# SCH_LED-bargraph-1_7_2024-11-25.net
KiCad netlist of a schematic drawn in EasyEDA
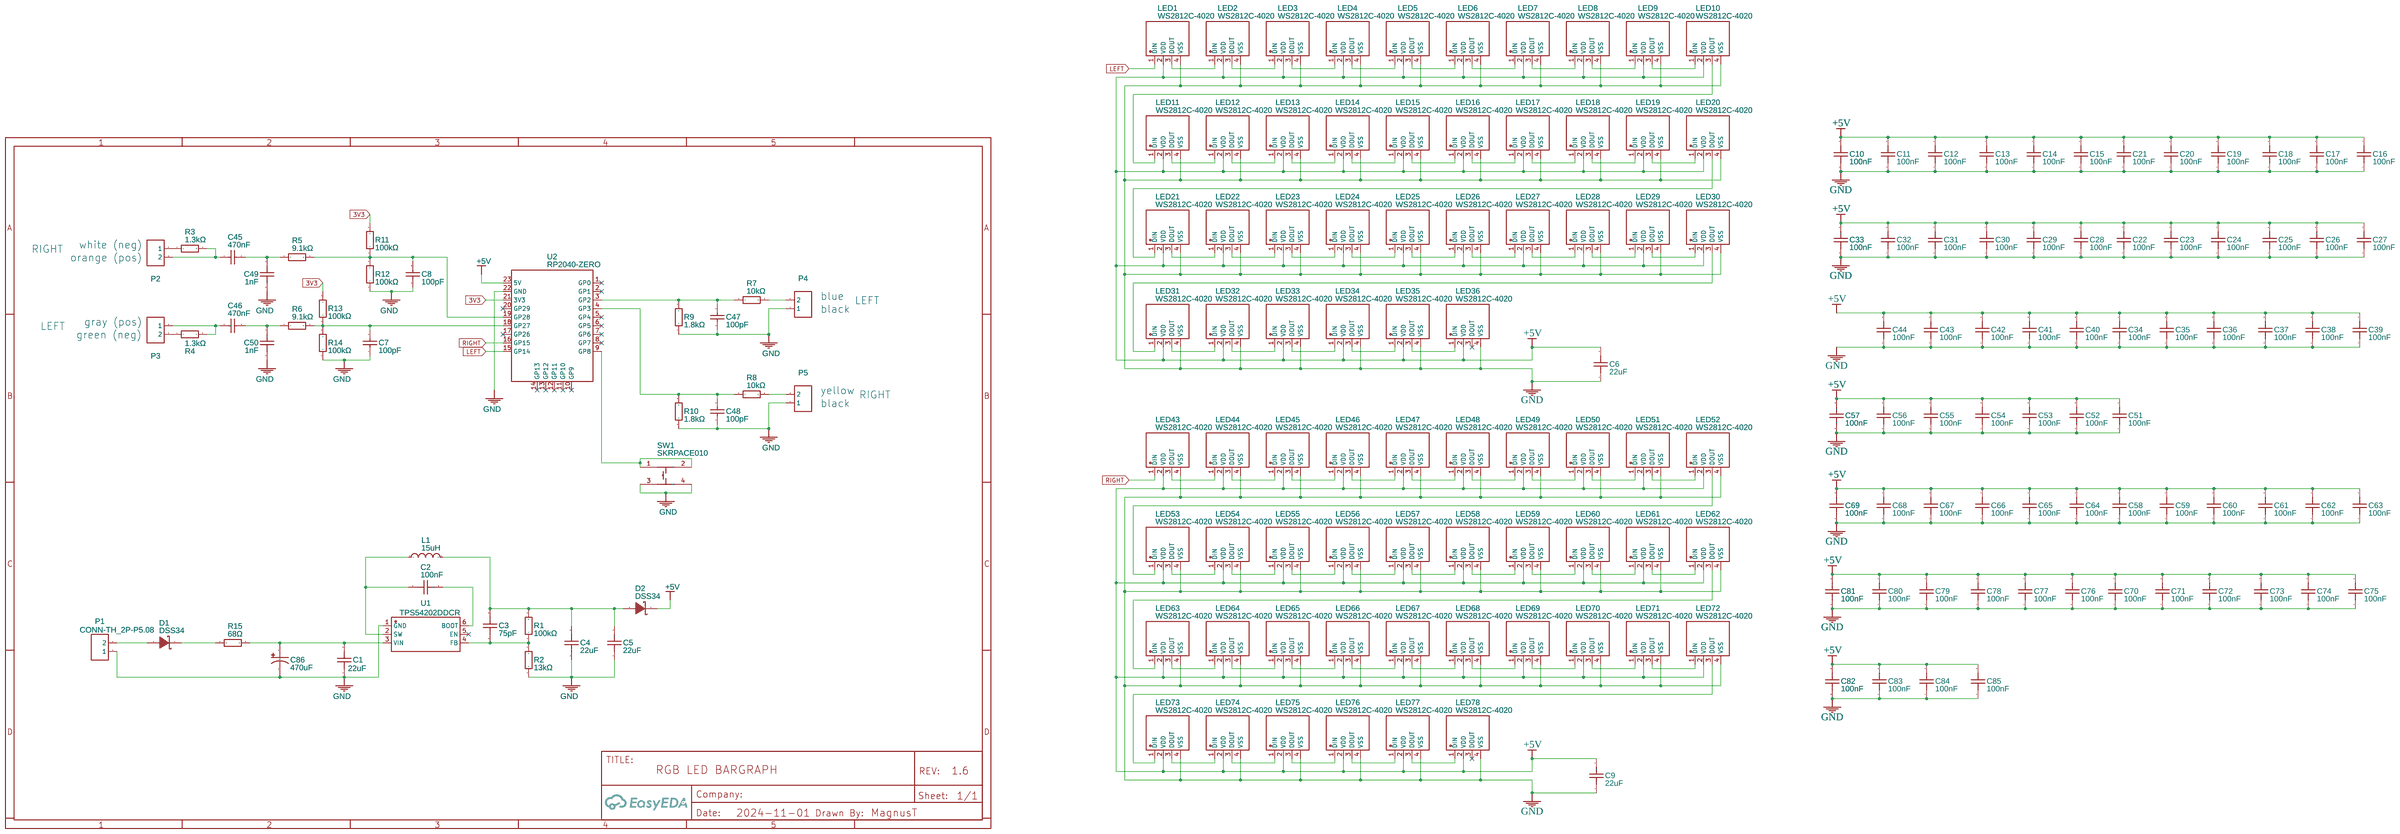
[diagram p0: schematic sheet]

(export (version "E")
  (design (tool "Eeschema 10.0.6"))
  (components
    (comp (ref "C1")
      (value "22uF")
      (fields
        (field (name "Manufacturer Part") "CL21A226MAYNNNE")
        (field (name "Manufacturer") "Samsung Electro-Mechanics")
      )
      (libsource (lib "") (part "CL21A226MAYNNNE"))
    )
    (comp (ref "C2")
      (value "100nF")
      (fields
        (field (name "Manufacturer Part") "CL05B104KO5NNNC")
        (field (name "Manufacturer") "SAMSUNG(三星)")
      )
      (libsource (lib "") (part "CL05B104KO5NNNC_1"))
    )
    (comp (ref "C3")
      (value "75pF")
      (fields
        (field (name "Manufacturer Part") "CC0603JRNPO9BN750")
        (field (name "Manufacturer") "YAGEO(国巨)")
      )
      (libsource (lib "") (part "CC0603JRNPO9BN750"))
    )
    (comp (ref "C4")
      (value "22uF")
      (fields (field (name "Manufacturer Part") "CL10A226MQ8NRNC") (field (name "Manufacturer") "SAMSUNG"))
      (libsource (lib "") (part "CL10A226MQ8NRNC"))
    )
    (comp (ref "C5")
      (value "22uF")
      (fields (field (name "Manufacturer Part") "CL10A226MQ8NRNC") (field (name "Manufacturer") "SAMSUNG"))
      (libsource (lib "") (part "CL10A226MQ8NRNC"))
    )
    (comp (ref "C6")
      (value "22uF")
      (fields (field (name "Manufacturer Part") "CL10A226MQ8NRNC") (field (name "Manufacturer") "SAMSUNG"))
      (libsource (lib "") (part "CL10A226MQ8NRNC"))
    )
    (comp (ref "C7")
      (value "100pF")
      (fields
        (field (name "Manufacturer Part") "CL10C101JB8NNNC")
        (field (name "Manufacturer") "SAMSUNG(三星)")
      )
      (libsource (lib "") (part "CL10C101JB8NNNC"))
    )
    (comp (ref "C8")
      (value "100pF")
      (fields
        (field (name "Manufacturer Part") "CL10C101JB8NNNC")
        (field (name "Manufacturer") "SAMSUNG(三星)")
      )
      (libsource (lib "") (part "CL10C101JB8NNNC"))
    )
    (comp (ref "C9")
      (value "22uF")
      (fields (field (name "Manufacturer Part") "CL10A226MQ8NRNC") (field (name "Manufacturer") "SAMSUNG"))
      (libsource (lib "") (part "CL10A226MQ8NRNC"))
    )
    (comp (ref "C10")
      (value "100nF")
      (fields
        (field (name "Manufacturer Part") "CL05B104KO5NNNC")
        (field (name "Manufacturer") "SAMSUNG(三星)")
      )
      (libsource (lib "") (part "CL05B104KO5NNNC"))
    )
    (comp (ref "C11")
      (value "100nF")
      (fields
        (field (name "Manufacturer Part") "CL05B104KO5NNNC")
        (field (name "Manufacturer") "SAMSUNG(三星)")
      )
      (libsource (lib "") (part "CL05B104KO5NNNC"))
    )
    (comp (ref "C12")
      (value "100nF")
      (fields
        (field (name "Manufacturer Part") "CL05B104KO5NNNC")
        (field (name "Manufacturer") "SAMSUNG(三星)")
      )
      (libsource (lib "") (part "CL05B104KO5NNNC"))
    )
    (comp (ref "C13")
      (value "100nF")
      (fields
        (field (name "Manufacturer Part") "CL05B104KO5NNNC")
        (field (name "Manufacturer") "SAMSUNG(三星)")
      )
      (libsource (lib "") (part "CL05B104KO5NNNC"))
    )
    (comp (ref "C14")
      (value "100nF")
      (fields
        (field (name "Manufacturer Part") "CL05B104KO5NNNC")
        (field (name "Manufacturer") "SAMSUNG(三星)")
      )
      (libsource (lib "") (part "CL05B104KO5NNNC"))
    )
    (comp (ref "C15")
      (value "100nF")
      (fields
        (field (name "Manufacturer Part") "CL05B104KO5NNNC")
        (field (name "Manufacturer") "SAMSUNG(三星)")
      )
      (libsource (lib "") (part "CL05B104KO5NNNC"))
    )
    (comp (ref "C16")
      (value "100nF")
      (fields
        (field (name "Manufacturer Part") "CL05B104KO5NNNC")
        (field (name "Manufacturer") "SAMSUNG(三星)")
      )
      (libsource (lib "") (part "CL05B104KO5NNNC"))
    )
    (comp (ref "C17")
      (value "100nF")
      (fields
        (field (name "Manufacturer Part") "CL05B104KO5NNNC")
        (field (name "Manufacturer") "SAMSUNG(三星)")
      )
      (libsource (lib "") (part "CL05B104KO5NNNC"))
    )
    (comp (ref "C18")
      (value "100nF")
      (fields
        (field (name "Manufacturer Part") "CL05B104KO5NNNC")
        (field (name "Manufacturer") "SAMSUNG(三星)")
      )
      (libsource (lib "") (part "CL05B104KO5NNNC"))
    )
    (comp (ref "C19")
      (value "100nF")
      (fields
        (field (name "Manufacturer Part") "CL05B104KO5NNNC")
        (field (name "Manufacturer") "SAMSUNG(三星)")
      )
      (libsource (lib "") (part "CL05B104KO5NNNC"))
    )
    (comp (ref "C20")
      (value "100nF")
      (fields
        (field (name "Manufacturer Part") "CL05B104KO5NNNC")
        (field (name "Manufacturer") "SAMSUNG(三星)")
      )
      (libsource (lib "") (part "CL05B104KO5NNNC"))
    )
    (comp (ref "C21")
      (value "100nF")
      (fields
        (field (name "Manufacturer Part") "CL05B104KO5NNNC")
        (field (name "Manufacturer") "SAMSUNG(三星)")
      )
      (libsource (lib "") (part "CL05B104KO5NNNC"))
    )
    (comp (ref "C22")
      (value "100nF")
      (fields
        (field (name "Manufacturer Part") "CL05B104KO5NNNC")
        (field (name "Manufacturer") "SAMSUNG(三星)")
      )
      (libsource (lib "") (part "CL05B104KO5NNNC"))
    )
    (comp (ref "C23")
      (value "100nF")
      (fields
        (field (name "Manufacturer Part") "CL05B104KO5NNNC")
        (field (name "Manufacturer") "SAMSUNG(三星)")
      )
      (libsource (lib "") (part "CL05B104KO5NNNC"))
    )
    (comp (ref "C24")
      (value "100nF")
      (fields
        (field (name "Manufacturer Part") "CL05B104KO5NNNC")
        (field (name "Manufacturer") "SAMSUNG(三星)")
      )
      (libsource (lib "") (part "CL05B104KO5NNNC"))
    )
    (comp (ref "C25")
      (value "100nF")
      (fields
        (field (name "Manufacturer Part") "CL05B104KO5NNNC")
        (field (name "Manufacturer") "SAMSUNG(三星)")
      )
      (libsource (lib "") (part "CL05B104KO5NNNC"))
    )
    (comp (ref "C26")
      (value "100nF")
      (fields
        (field (name "Manufacturer Part") "CL05B104KO5NNNC")
        (field (name "Manufacturer") "SAMSUNG(三星)")
      )
      (libsource (lib "") (part "CL05B104KO5NNNC"))
    )
    (comp (ref "C27")
      (value "100nF")
      (fields
        (field (name "Manufacturer Part") "CL05B104KO5NNNC")
        (field (name "Manufacturer") "SAMSUNG(三星)")
      )
      (libsource (lib "") (part "CL05B104KO5NNNC"))
    )
    (comp (ref "C28")
      (value "100nF")
      (fields
        (field (name "Manufacturer Part") "CL05B104KO5NNNC")
        (field (name "Manufacturer") "SAMSUNG(三星)")
      )
      (libsource (lib "") (part "CL05B104KO5NNNC"))
    )
    (comp (ref "C29")
      (value "100nF")
      (fields
        (field (name "Manufacturer Part") "CL05B104KO5NNNC")
        (field (name "Manufacturer") "SAMSUNG(三星)")
      )
      (libsource (lib "") (part "CL05B104KO5NNNC"))
    )
    (comp (ref "C30")
      (value "100nF")
      (fields
        (field (name "Manufacturer Part") "CL05B104KO5NNNC")
        (field (name "Manufacturer") "SAMSUNG(三星)")
      )
      (libsource (lib "") (part "CL05B104KO5NNNC"))
    )
    (comp (ref "C31")
      (value "100nF")
      (fields
        (field (name "Manufacturer Part") "CL05B104KO5NNNC")
        (field (name "Manufacturer") "SAMSUNG(三星)")
      )
      (libsource (lib "") (part "CL05B104KO5NNNC"))
    )
    (comp (ref "C32")
      (value "100nF")
      (fields
        (field (name "Manufacturer Part") "CL05B104KO5NNNC")
        (field (name "Manufacturer") "SAMSUNG(三星)")
      )
      (libsource (lib "") (part "CL05B104KO5NNNC"))
    )
    (comp (ref "C33")
      (value "100nF")
      (fields
        (field (name "Manufacturer Part") "CL05B104KO5NNNC")
        (field (name "Manufacturer") "SAMSUNG(三星)")
      )
      (libsource (lib "") (part "CL05B104KO5NNNC"))
    )
    (comp (ref "C34")
      (value "100nF")
      (fields
        (field (name "Manufacturer Part") "CL05B104KO5NNNC")
        (field (name "Manufacturer") "SAMSUNG(三星)")
      )
      (libsource (lib "") (part "CL05B104KO5NNNC"))
    )
    (comp (ref "C35")
      (value "100nF")
      (fields
        (field (name "Manufacturer Part") "CL05B104KO5NNNC")
        (field (name "Manufacturer") "SAMSUNG(三星)")
      )
      (libsource (lib "") (part "CL05B104KO5NNNC"))
    )
    (comp (ref "C36")
      (value "100nF")
      (fields
        (field (name "Manufacturer Part") "CL05B104KO5NNNC")
        (field (name "Manufacturer") "SAMSUNG(三星)")
      )
      (libsource (lib "") (part "CL05B104KO5NNNC"))
    )
    (comp (ref "C37")
      (value "100nF")
      (fields
        (field (name "Manufacturer Part") "CL05B104KO5NNNC")
        (field (name "Manufacturer") "SAMSUNG(三星)")
      )
      (libsource (lib "") (part "CL05B104KO5NNNC"))
    )
    (comp (ref "C38")
      (value "100nF")
      (fields
        (field (name "Manufacturer Part") "CL05B104KO5NNNC")
        (field (name "Manufacturer") "SAMSUNG(三星)")
      )
      (libsource (lib "") (part "CL05B104KO5NNNC"))
    )
    (comp (ref "C39")
      (value "100nF")
      (fields
        (field (name "Manufacturer Part") "CL05B104KO5NNNC")
        (field (name "Manufacturer") "SAMSUNG(三星)")
      )
      (libsource (lib "") (part "CL05B104KO5NNNC"))
    )
    (comp (ref "C40")
      (value "100nF")
      (fields
        (field (name "Manufacturer Part") "CL05B104KO5NNNC")
        (field (name "Manufacturer") "SAMSUNG(三星)")
      )
      (libsource (lib "") (part "CL05B104KO5NNNC"))
    )
    (comp (ref "C41")
      (value "100nF")
      (fields
        (field (name "Manufacturer Part") "CL05B104KO5NNNC")
        (field (name "Manufacturer") "SAMSUNG(三星)")
      )
      (libsource (lib "") (part "CL05B104KO5NNNC"))
    )
    (comp (ref "C42")
      (value "100nF")
      (fields
        (field (name "Manufacturer Part") "CL05B104KO5NNNC")
        (field (name "Manufacturer") "SAMSUNG(三星)")
      )
      (libsource (lib "") (part "CL05B104KO5NNNC"))
    )
    (comp (ref "C43")
      (value "100nF")
      (fields
        (field (name "Manufacturer Part") "CL05B104KO5NNNC")
        (field (name "Manufacturer") "SAMSUNG(三星)")
      )
      (libsource (lib "") (part "CL05B104KO5NNNC"))
    )
    (comp (ref "C44")
      (value "100nF")
      (fields
        (field (name "Manufacturer Part") "CL05B104KO5NNNC")
        (field (name "Manufacturer") "SAMSUNG(三星)")
      )
      (libsource (lib "") (part "CL05B104KO5NNNC"))
    )
    (comp (ref "C45")
      (value "470nF")
      (fields
        (field (name "Manufacturer Part") "CL21B474KBFNNNE")
        (field (name "Manufacturer") "SAMSUNG(三星)")
      )
      (libsource (lib "") (part "CL21B474KBFNNNE"))
    )
    (comp (ref "C46")
      (value "470nF")
      (fields
        (field (name "Manufacturer Part") "CL21B474KBFNNNE")
        (field (name "Manufacturer") "SAMSUNG(三星)")
      )
      (libsource (lib "") (part "CL21B474KBFNNNE"))
    )
    (comp (ref "C47")
      (value "100pF")
      (fields
        (field (name "Manufacturer Part") "CL10C101JB8NNNC")
        (field (name "Manufacturer") "SAMSUNG(三星)")
      )
      (libsource (lib "") (part "CL10C101JB8NNNC"))
    )
    (comp (ref "C48")
      (value "100pF")
      (fields
        (field (name "Manufacturer Part") "CL10C101JB8NNNC")
        (field (name "Manufacturer") "SAMSUNG(三星)")
      )
      (libsource (lib "") (part "CL10C101JB8NNNC"))
    )
    (comp (ref "C49")
      (value "1nF")
      (fields
        (field (name "Manufacturer Part") "CL10C102JB8NNNC")
        (field (name "Manufacturer") "SAMSUNG(三星)")
      )
      (libsource (lib "") (part "CL10C102JB8NNNC"))
    )
    (comp (ref "C50")
      (value "1nF")
      (fields
        (field (name "Manufacturer Part") "CL10C102JB8NNNC")
        (field (name "Manufacturer") "SAMSUNG(三星)")
      )
      (libsource (lib "") (part "CL10C102JB8NNNC"))
    )
    (comp (ref "C51")
      (value "100nF")
      (fields
        (field (name "Manufacturer Part") "CL05B104KO5NNNC")
        (field (name "Manufacturer") "SAMSUNG(三星)")
      )
      (libsource (lib "") (part "CL05B104KO5NNNC"))
    )
    (comp (ref "C52")
      (value "100nF")
      (fields
        (field (name "Manufacturer Part") "CL05B104KO5NNNC")
        (field (name "Manufacturer") "SAMSUNG(三星)")
      )
      (libsource (lib "") (part "CL05B104KO5NNNC"))
    )
    (comp (ref "C53")
      (value "100nF")
      (fields
        (field (name "Manufacturer Part") "CL05B104KO5NNNC")
        (field (name "Manufacturer") "SAMSUNG(三星)")
      )
      (libsource (lib "") (part "CL05B104KO5NNNC"))
    )
    (comp (ref "C54")
      (value "100nF")
      (fields
        (field (name "Manufacturer Part") "CL05B104KO5NNNC")
        (field (name "Manufacturer") "SAMSUNG(三星)")
      )
      (libsource (lib "") (part "CL05B104KO5NNNC"))
    )
    (comp (ref "C55")
      (value "100nF")
      (fields
        (field (name "Manufacturer Part") "CL05B104KO5NNNC")
        (field (name "Manufacturer") "SAMSUNG(三星)")
      )
      (libsource (lib "") (part "CL05B104KO5NNNC"))
    )
    (comp (ref "C56")
      (value "100nF")
      (fields
        (field (name "Manufacturer Part") "CL05B104KO5NNNC")
        (field (name "Manufacturer") "SAMSUNG(三星)")
      )
      (libsource (lib "") (part "CL05B104KO5NNNC"))
    )
    (comp (ref "C57")
      (value "100nF")
      (fields
        (field (name "Manufacturer Part") "CL05B104KO5NNNC")
        (field (name "Manufacturer") "SAMSUNG(三星)")
      )
      (libsource (lib "") (part "CL05B104KO5NNNC"))
    )
    (comp (ref "C58")
      (value "100nF")
      (fields
        (field (name "Manufacturer Part") "CL05B104KO5NNNC")
        (field (name "Manufacturer") "SAMSUNG(三星)")
      )
      (libsource (lib "") (part "CL05B104KO5NNNC"))
    )
    (comp (ref "C59")
      (value "100nF")
      (fields
        (field (name "Manufacturer Part") "CL05B104KO5NNNC")
        (field (name "Manufacturer") "SAMSUNG(三星)")
      )
      (libsource (lib "") (part "CL05B104KO5NNNC"))
    )
    (comp (ref "C60")
      (value "100nF")
      (fields
        (field (name "Manufacturer Part") "CL05B104KO5NNNC")
        (field (name "Manufacturer") "SAMSUNG(三星)")
      )
      (libsource (lib "") (part "CL05B104KO5NNNC"))
    )
    (comp (ref "C61")
      (value "100nF")
      (fields
        (field (name "Manufacturer Part") "CL05B104KO5NNNC")
        (field (name "Manufacturer") "SAMSUNG(三星)")
      )
      (libsource (lib "") (part "CL05B104KO5NNNC"))
    )
    (comp (ref "C62")
      (value "100nF")
      (fields
        (field (name "Manufacturer Part") "CL05B104KO5NNNC")
        (field (name "Manufacturer") "SAMSUNG(三星)")
      )
      (libsource (lib "") (part "CL05B104KO5NNNC"))
    )
    (comp (ref "C63")
      (value "100nF")
      (fields
        (field (name "Manufacturer Part") "CL05B104KO5NNNC")
        (field (name "Manufacturer") "SAMSUNG(三星)")
      )
      (libsource (lib "") (part "CL05B104KO5NNNC"))
    )
    (comp (ref "C64")
      (value "100nF")
      (fields
        (field (name "Manufacturer Part") "CL05B104KO5NNNC")
        (field (name "Manufacturer") "SAMSUNG(三星)")
      )
      (libsource (lib "") (part "CL05B104KO5NNNC"))
    )
    (comp (ref "C65")
      (value "100nF")
      (fields
        (field (name "Manufacturer Part") "CL05B104KO5NNNC")
        (field (name "Manufacturer") "SAMSUNG(三星)")
      )
      (libsource (lib "") (part "CL05B104KO5NNNC"))
    )
    (comp (ref "C66")
      (value "100nF")
      (fields
        (field (name "Manufacturer Part") "CL05B104KO5NNNC")
        (field (name "Manufacturer") "SAMSUNG(三星)")
      )
      (libsource (lib "") (part "CL05B104KO5NNNC"))
    )
    (comp (ref "C67")
      (value "100nF")
      (fields
        (field (name "Manufacturer Part") "CL05B104KO5NNNC")
        (field (name "Manufacturer") "SAMSUNG(三星)")
      )
      (libsource (lib "") (part "CL05B104KO5NNNC"))
    )
    (comp (ref "C68")
      (value "100nF")
      (fields
        (field (name "Manufacturer Part") "CL05B104KO5NNNC")
        (field (name "Manufacturer") "SAMSUNG(三星)")
      )
      (libsource (lib "") (part "CL05B104KO5NNNC"))
    )
    (comp (ref "C69")
      (value "100nF")
      (fields
        (field (name "Manufacturer Part") "CL05B104KO5NNNC")
        (field (name "Manufacturer") "SAMSUNG(三星)")
      )
      (libsource (lib "") (part "CL05B104KO5NNNC"))
    )
    (comp (ref "C70")
      (value "100nF")
      (fields
        (field (name "Manufacturer Part") "CL05B104KO5NNNC")
        (field (name "Manufacturer") "SAMSUNG(三星)")
      )
      (libsource (lib "") (part "CL05B104KO5NNNC"))
    )
    (comp (ref "C71")
      (value "100nF")
      (fields
        (field (name "Manufacturer Part") "CL05B104KO5NNNC")
        (field (name "Manufacturer") "SAMSUNG(三星)")
      )
      (libsource (lib "") (part "CL05B104KO5NNNC"))
    )
    (comp (ref "C72")
      (value "100nF")
      (fields
        (field (name "Manufacturer Part") "CL05B104KO5NNNC")
        (field (name "Manufacturer") "SAMSUNG(三星)")
      )
      (libsource (lib "") (part "CL05B104KO5NNNC"))
    )
    (comp (ref "C73")
      (value "100nF")
      (fields
        (field (name "Manufacturer Part") "CL05B104KO5NNNC")
        (field (name "Manufacturer") "SAMSUNG(三星)")
      )
      (libsource (lib "") (part "CL05B104KO5NNNC"))
    )
    (comp (ref "C74")
      (value "100nF")
      (fields
        (field (name "Manufacturer Part") "CL05B104KO5NNNC")
        (field (name "Manufacturer") "SAMSUNG(三星)")
      )
      (libsource (lib "") (part "CL05B104KO5NNNC"))
    )
    (comp (ref "C75")
      (value "100nF")
      (fields
        (field (name "Manufacturer Part") "CL05B104KO5NNNC")
        (field (name "Manufacturer") "SAMSUNG(三星)")
      )
      (libsource (lib "") (part "CL05B104KO5NNNC"))
    )
    (comp (ref "C76")
      (value "100nF")
      (fields
        (field (name "Manufacturer Part") "CL05B104KO5NNNC")
        (field (name "Manufacturer") "SAMSUNG(三星)")
      )
      (libsource (lib "") (part "CL05B104KO5NNNC"))
    )
    (comp (ref "C77")
      (value "100nF")
      (fields
        (field (name "Manufacturer Part") "CL05B104KO5NNNC")
        (field (name "Manufacturer") "SAMSUNG(三星)")
      )
      (libsource (lib "") (part "CL05B104KO5NNNC"))
    )
    (comp (ref "C78")
      (value "100nF")
      (fields
        (field (name "Manufacturer Part") "CL05B104KO5NNNC")
        (field (name "Manufacturer") "SAMSUNG(三星)")
      )
      (libsource (lib "") (part "CL05B104KO5NNNC"))
    )
    (comp (ref "C79")
      (value "100nF")
      (fields
        (field (name "Manufacturer Part") "CL05B104KO5NNNC")
        (field (name "Manufacturer") "SAMSUNG(三星)")
      )
      (libsource (lib "") (part "CL05B104KO5NNNC"))
    )
    (comp (ref "C80")
      (value "100nF")
      (fields
        (field (name "Manufacturer Part") "CL05B104KO5NNNC")
        (field (name "Manufacturer") "SAMSUNG(三星)")
      )
      (libsource (lib "") (part "CL05B104KO5NNNC"))
    )
    (comp (ref "C81")
      (value "100nF")
      (fields
        (field (name "Manufacturer Part") "CL05B104KO5NNNC")
        (field (name "Manufacturer") "SAMSUNG(三星)")
      )
      (libsource (lib "") (part "CL05B104KO5NNNC"))
    )
    (comp (ref "C82")
      (value "100nF")
      (fields
        (field (name "Manufacturer Part") "CL05B104KO5NNNC")
        (field (name "Manufacturer") "SAMSUNG(三星)")
      )
      (libsource (lib "") (part "CL05B104KO5NNNC"))
    )
    (comp (ref "C83")
      (value "100nF")
      (fields
        (field (name "Manufacturer Part") "CL05B104KO5NNNC")
        (field (name "Manufacturer") "SAMSUNG(三星)")
      )
      (libsource (lib "") (part "CL05B104KO5NNNC"))
    )
    (comp (ref "C84")
      (value "100nF")
      (fields
        (field (name "Manufacturer Part") "CL05B104KO5NNNC")
        (field (name "Manufacturer") "SAMSUNG(三星)")
      )
      (libsource (lib "") (part "CL05B104KO5NNNC"))
    )
    (comp (ref "C85")
      (value "100nF")
      (fields
        (field (name "Manufacturer Part") "CL05B104KO5NNNC")
        (field (name "Manufacturer") "SAMSUNG(三星)")
      )
      (libsource (lib "") (part "CL05B104KO5NNNC"))
    )
    (comp (ref "C86")
      (value "470uF")
      (fields (field (name "Manufacturer Part") "RVT1A471M0607") (field (name "Manufacturer") "ROQANG(容强)"))
      (libsource (lib "") (part "RVT1A471M0607_C335982"))
    )
    (comp (ref "D1")
      (value "DSS34")
      (fields (field (name "Manufacturer") "STARSEA"))
      (libsource (lib "") (part "DSS34"))
    )
    (comp (ref "D2")
      (value "DSS34")
      (fields (field (name "Manufacturer") "STARSEA"))
      (libsource (lib "") (part "DSS34"))
    )
    (comp (ref "L1")
      (value "15uH")
      (fields
        (field (name "Manufacturer Part") "SLP6028S150MTT")
        (field (name "Manufacturer") "Sunltech(韩国顺磁)")
      )
      (libsource (lib "") (part "SLP6028S150MTT"))
    )
    (comp (ref "LED1")
      (value "WS2812C-4020")
      (fields (field (name "Manufacturer") "worldsemi"))
      (libsource (lib "") (part "WS2812C-4020"))
    )
    (comp (ref "LED2")
      (value "WS2812C-4020")
      (fields (field (name "Manufacturer") "worldsemi"))
      (libsource (lib "") (part "WS2812C-4020"))
    )
    (comp (ref "LED3")
      (value "WS2812C-4020")
      (fields (field (name "Manufacturer") "worldsemi"))
      (libsource (lib "") (part "WS2812C-4020"))
    )
    (comp (ref "LED4")
      (value "WS2812C-4020")
      (fields (field (name "Manufacturer") "worldsemi"))
      (libsource (lib "") (part "WS2812C-4020"))
    )
    (comp (ref "LED5")
      (value "WS2812C-4020")
      (fields (field (name "Manufacturer") "worldsemi"))
      (libsource (lib "") (part "WS2812C-4020"))
    )
    (comp (ref "LED6")
      (value "WS2812C-4020")
      (fields (field (name "Manufacturer") "worldsemi"))
      (libsource (lib "") (part "WS2812C-4020"))
    )
    (comp (ref "LED7")
      (value "WS2812C-4020")
      (fields (field (name "Manufacturer") "worldsemi"))
      (libsource (lib "") (part "WS2812C-4020"))
    )
    (comp (ref "LED8")
      (value "WS2812C-4020")
      (fields (field (name "Manufacturer") "worldsemi"))
      (libsource (lib "") (part "WS2812C-4020"))
    )
    (comp (ref "LED9")
      (value "WS2812C-4020")
      (fields (field (name "Manufacturer") "worldsemi"))
      (libsource (lib "") (part "WS2812C-4020"))
    )
    (comp (ref "LED10")
      (value "WS2812C-4020")
      (fields (field (name "Manufacturer") "worldsemi"))
      (libsource (lib "") (part "WS2812C-4020"))
    )
    (comp (ref "LED11")
      (value "WS2812C-4020")
      (fields (field (name "Manufacturer") "worldsemi"))
      (libsource (lib "") (part "WS2812C-4020"))
    )
    (comp (ref "LED12")
      (value "WS2812C-4020")
      (fields (field (name "Manufacturer") "worldsemi"))
      (libsource (lib "") (part "WS2812C-4020"))
    )
    (comp (ref "LED13")
      (value "WS2812C-4020")
      (fields (field (name "Manufacturer") "worldsemi"))
      (libsource (lib "") (part "WS2812C-4020"))
    )
    (comp (ref "LED14")
      (value "WS2812C-4020")
      (fields (field (name "Manufacturer") "worldsemi"))
      (libsource (lib "") (part "WS2812C-4020"))
    )
    (comp (ref "LED15")
      (value "WS2812C-4020")
      (fields (field (name "Manufacturer") "worldsemi"))
      (libsource (lib "") (part "WS2812C-4020"))
    )
    (comp (ref "LED16")
      (value "WS2812C-4020")
      (fields (field (name "Manufacturer") "worldsemi"))
      (libsource (lib "") (part "WS2812C-4020"))
    )
    (comp (ref "LED17")
      (value "WS2812C-4020")
      (fields (field (name "Manufacturer") "worldsemi"))
      (libsource (lib "") (part "WS2812C-4020"))
    )
    (comp (ref "LED18")
      (value "WS2812C-4020")
      (fields (field (name "Manufacturer") "worldsemi"))
      (libsource (lib "") (part "WS2812C-4020"))
    )
    (comp (ref "LED19")
      (value "WS2812C-4020")
      (fields (field (name "Manufacturer") "worldsemi"))
      (libsource (lib "") (part "WS2812C-4020"))
    )
    (comp (ref "LED20")
      (value "WS2812C-4020")
      (fields (field (name "Manufacturer") "worldsemi"))
      (libsource (lib "") (part "WS2812C-4020"))
    )
    (comp (ref "LED21")
      (value "WS2812C-4020")
      (fields (field (name "Manufacturer") "worldsemi"))
      (libsource (lib "") (part "WS2812C-4020"))
    )
    (comp (ref "LED22")
      (value "WS2812C-4020")
      (fields (field (name "Manufacturer") "worldsemi"))
      (libsource (lib "") (part "WS2812C-4020"))
    )
    (comp (ref "LED23")
      (value "WS2812C-4020")
      (fields (field (name "Manufacturer") "worldsemi"))
      (libsource (lib "") (part "WS2812C-4020"))
    )
    (comp (ref "LED24")
      (value "WS2812C-4020")
      (fields (field (name "Manufacturer") "worldsemi"))
      (libsource (lib "") (part "WS2812C-4020"))
    )
    (comp (ref "LED25")
      (value "WS2812C-4020")
      (fields (field (name "Manufacturer") "worldsemi"))
      (libsource (lib "") (part "WS2812C-4020"))
    )
    (comp (ref "LED26")
      (value "WS2812C-4020")
      (fields (field (name "Manufacturer") "worldsemi"))
      (libsource (lib "") (part "WS2812C-4020"))
    )
    (comp (ref "LED27")
      (value "WS2812C-4020")
      (fields (field (name "Manufacturer") "worldsemi"))
      (libsource (lib "") (part "WS2812C-4020"))
    )
    (comp (ref "LED28")
      (value "WS2812C-4020")
      (fields (field (name "Manufacturer") "worldsemi"))
      (libsource (lib "") (part "WS2812C-4020"))
    )
    (comp (ref "LED29")
      (value "WS2812C-4020")
      (fields (field (name "Manufacturer") "worldsemi"))
      (libsource (lib "") (part "WS2812C-4020"))
    )
    (comp (ref "LED30")
      (value "WS2812C-4020")
      (fields (field (name "Manufacturer") "worldsemi"))
      (libsource (lib "") (part "WS2812C-4020"))
    )
    (comp (ref "LED31")
      (value "WS2812C-4020")
      (fields (field (name "Manufacturer") "worldsemi"))
      (libsource (lib "") (part "WS2812C-4020"))
    )
    (comp (ref "LED32")
      (value "WS2812C-4020")
      (fields (field (name "Manufacturer") "worldsemi"))
      (libsource (lib "") (part "WS2812C-4020"))
    )
    (comp (ref "LED33")
      (value "WS2812C-4020")
      (fields (field (name "Manufacturer") "worldsemi"))
      (libsource (lib "") (part "WS2812C-4020"))
    )
    (comp (ref "LED34")
      (value "WS2812C-4020")
      (fields (field (name "Manufacturer") "worldsemi"))
      (libsource (lib "") (part "WS2812C-4020"))
    )
    (comp (ref "LED35")
      (value "WS2812C-4020")
      (fields (field (name "Manufacturer") "worldsemi"))
      (libsource (lib "") (part "WS2812C-4020"))
    )
    (comp (ref "LED36")
      (value "WS2812C-4020")
      (fields (field (name "Manufacturer") "worldsemi"))
      (libsource (lib "") (part "WS2812C-4020"))
    )
    (comp (ref "LED43")
      (value "WS2812C-4020")
      (fields (field (name "Manufacturer") "worldsemi"))
      (libsource (lib "") (part "WS2812C-4020"))
    )
    (comp (ref "LED44")
      (value "WS2812C-4020")
      (fields (field (name "Manufacturer") "worldsemi"))
      (libsource (lib "") (part "WS2812C-4020"))
    )
    (comp (ref "LED45")
      (value "WS2812C-4020")
      (fields (field (name "Manufacturer") "worldsemi"))
      (libsource (lib "") (part "WS2812C-4020"))
    )
    (comp (ref "LED46")
      (value "WS2812C-4020")
      (fields (field (name "Manufacturer") "worldsemi"))
      (libsource (lib "") (part "WS2812C-4020"))
    )
    (comp (ref "LED47")
      (value "WS2812C-4020")
      (fields (field (name "Manufacturer") "worldsemi"))
      (libsource (lib "") (part "WS2812C-4020"))
    )
    (comp (ref "LED48")
      (value "WS2812C-4020")
      (fields (field (name "Manufacturer") "worldsemi"))
      (libsource (lib "") (part "WS2812C-4020"))
    )
    (comp (ref "LED49")
      (value "WS2812C-4020")
      (fields (field (name "Manufacturer") "worldsemi"))
      (libsource (lib "") (part "WS2812C-4020"))
    )
    (comp (ref "LED50")
      (value "WS2812C-4020")
      (fields (field (name "Manufacturer") "worldsemi"))
      (libsource (lib "") (part "WS2812C-4020"))
    )
    (comp (ref "LED51")
      (value "WS2812C-4020")
      (fields (field (name "Manufacturer") "worldsemi"))
      (libsource (lib "") (part "WS2812C-4020"))
    )
    (comp (ref "LED52")
      (value "WS2812C-4020")
      (fields (field (name "Manufacturer") "worldsemi"))
      (libsource (lib "") (part "WS2812C-4020"))
    )
    (comp (ref "LED53")
      (value "WS2812C-4020")
      (fields (field (name "Manufacturer") "worldsemi"))
      (libsource (lib "") (part "WS2812C-4020"))
    )
    (comp (ref "LED54")
      (value "WS2812C-4020")
      (fields (field (name "Manufacturer") "worldsemi"))
      (libsource (lib "") (part "WS2812C-4020"))
    )
    (comp (ref "LED55")
      (value "WS2812C-4020")
      (fields (field (name "Manufacturer") "worldsemi"))
      (libsource (lib "") (part "WS2812C-4020"))
    )
    (comp (ref "LED56")
      (value "WS2812C-4020")
      (fields (field (name "Manufacturer") "worldsemi"))
      (libsource (lib "") (part "WS2812C-4020"))
    )
    (comp (ref "LED57")
      (value "WS2812C-4020")
      (fields (field (name "Manufacturer") "worldsemi"))
      (libsource (lib "") (part "WS2812C-4020"))
    )
    (comp (ref "LED58")
      (value "WS2812C-4020")
      (fields (field (name "Manufacturer") "worldsemi"))
      (libsource (lib "") (part "WS2812C-4020"))
    )
    (comp (ref "LED59")
      (value "WS2812C-4020")
      (fields (field (name "Manufacturer") "worldsemi"))
      (libsource (lib "") (part "WS2812C-4020"))
    )
    (comp (ref "LED60")
      (value "WS2812C-4020")
      (fields (field (name "Manufacturer") "worldsemi"))
      (libsource (lib "") (part "WS2812C-4020"))
    )
    (comp (ref "LED61")
      (value "WS2812C-4020")
      (fields (field (name "Manufacturer") "worldsemi"))
      (libsource (lib "") (part "WS2812C-4020"))
    )
    (comp (ref "LED62")
      (value "WS2812C-4020")
      (fields (field (name "Manufacturer") "worldsemi"))
      (libsource (lib "") (part "WS2812C-4020"))
    )
    (comp (ref "LED63")
      (value "WS2812C-4020")
      (fields (field (name "Manufacturer") "worldsemi"))
      (libsource (lib "") (part "WS2812C-4020"))
    )
    (comp (ref "LED64")
      (value "WS2812C-4020")
      (fields (field (name "Manufacturer") "worldsemi"))
      (libsource (lib "") (part "WS2812C-4020"))
    )
    (comp (ref "LED65")
      (value "WS2812C-4020")
      (fields (field (name "Manufacturer") "worldsemi"))
      (libsource (lib "") (part "WS2812C-4020"))
    )
    (comp (ref "LED66")
      (value "WS2812C-4020")
      (fields (field (name "Manufacturer") "worldsemi"))
      (libsource (lib "") (part "WS2812C-4020"))
    )
    (comp (ref "LED67")
      (value "WS2812C-4020")
      (fields (field (name "Manufacturer") "worldsemi"))
      (libsource (lib "") (part "WS2812C-4020"))
    )
    (comp (ref "LED68")
      (value "WS2812C-4020")
      (fields (field (name "Manufacturer") "worldsemi"))
      (libsource (lib "") (part "WS2812C-4020"))
    )
    (comp (ref "LED69")
      (value "WS2812C-4020")
      (fields (field (name "Manufacturer") "worldsemi"))
      (libsource (lib "") (part "WS2812C-4020"))
    )
    (comp (ref "LED70")
      (value "WS2812C-4020")
      (fields (field (name "Manufacturer") "worldsemi"))
      (libsource (lib "") (part "WS2812C-4020"))
    )
    (comp (ref "LED71")
      (value "WS2812C-4020")
      (fields (field (name "Manufacturer") "worldsemi"))
      (libsource (lib "") (part "WS2812C-4020"))
    )
    (comp (ref "LED72")
      (value "WS2812C-4020")
      (fields (field (name "Manufacturer") "worldsemi"))
      (libsource (lib "") (part "WS2812C-4020"))
    )
    (comp (ref "LED73")
      (value "WS2812C-4020")
      (fields (field (name "Manufacturer") "worldsemi"))
      (libsource (lib "") (part "WS2812C-4020"))
    )
    (comp (ref "LED74")
      (value "WS2812C-4020")
      (fields (field (name "Manufacturer") "worldsemi"))
      (libsource (lib "") (part "WS2812C-4020"))
    )
    (comp (ref "LED75")
      (value "WS2812C-4020")
      (fields (field (name "Manufacturer") "worldsemi"))
      (libsource (lib "") (part "WS2812C-4020"))
    )
    (comp (ref "LED76")
      (value "WS2812C-4020")
      (fields (field (name "Manufacturer") "worldsemi"))
      (libsource (lib "") (part "WS2812C-4020"))
    )
    (comp (ref "LED77")
      (value "WS2812C-4020")
      (fields (field (name "Manufacturer") "worldsemi"))
      (libsource (lib "") (part "WS2812C-4020"))
    )
    (comp (ref "LED78")
      (value "WS2812C-4020")
      (fields (field (name "Manufacturer") "worldsemi"))
      (libsource (lib "") (part "WS2812C-4020"))
    )
    (comp (ref "P1") (value "CONN-TH_2P-P5.08") (libsource (lib "") (part "CONN-TH_2P-P5.08")))
    (comp (ref "P2") (value "CONN-TH_2P-P5.08") (libsource (lib "") (part "CONN-TH_2P-P5.08_2")))
    (comp (ref "P3") (value "CONN-TH_2P-P5.08") (libsource (lib "") (part "CONN-TH_2P-P5.08_2")))
    (comp (ref "P4") (value "CONN-TH_2P-P5.08") (libsource (lib "") (part "CONN-TH_2P-P5.08_1")))
    (comp (ref "P5") (value "CONN-TH_2P-P5.08") (libsource (lib "") (part "CONN-TH_2P-P5.08_1")))
    (comp (ref "R1")
      (value "100kΩ")
      (fields
        (field (name "Manufacturer Part") "0603WAF1003T5E")
        (field (name "Manufacturer") "UNI-ROYAL(厚声)")
      )
      (libsource (lib "") (part "0603WAF1003T5E"))
    )
    (comp (ref "R2")
      (value "13kΩ")
      (fields
        (field (name "Manufacturer Part") "0603WAF1302T5E")
        (field (name "Manufacturer") "UNI-ROYAL(厚声)")
      )
      (libsource (lib "") (part "0603WAF1302T5E"))
    )
    (comp (ref "R3")
      (value "1.3kΩ")
      (fields
        (field (name "Manufacturer Part") "0603WAF1301T5E")
        (field (name "Manufacturer") "UNI-ROYAL(厚声)")
      )
      (libsource (lib "") (part "0603WAF1301T5E"))
    )
    (comp (ref "R4")
      (value "1.3kΩ")
      (fields
        (field (name "Manufacturer Part") "0603WAF1301T5E")
        (field (name "Manufacturer") "UNI-ROYAL(厚声)")
      )
      (libsource (lib "") (part "0603WAF1301T5E"))
    )
    (comp (ref "R5")
      (value "9.1kΩ")
      (fields
        (field (name "Manufacturer Part") "0603WAF9101T5E")
        (field (name "Manufacturer") "UNI-ROYAL(厚声)")
      )
      (libsource (lib "") (part "0603WAF9101T5E"))
    )
    (comp (ref "R6")
      (value "9.1kΩ")
      (fields
        (field (name "Manufacturer Part") "0603WAF9101T5E")
        (field (name "Manufacturer") "UNI-ROYAL(厚声)")
      )
      (libsource (lib "") (part "0603WAF9101T5E"))
    )
    (comp (ref "R7")
      (value "10kΩ")
      (fields
        (field (name "Manufacturer Part") "0603WAF1002T5E")
        (field (name "Manufacturer") "UNI-ROYAL(厚声)")
      )
      (libsource (lib "") (part "0603WAF1002T5E"))
    )
    (comp (ref "R8")
      (value "10kΩ")
      (fields
        (field (name "Manufacturer Part") "0603WAF1002T5E")
        (field (name "Manufacturer") "UNI-ROYAL(厚声)")
      )
      (libsource (lib "") (part "0603WAF1002T5E"))
    )
    (comp (ref "R9")
      (value "1.8kΩ")
      (fields
        (field (name "Manufacturer Part") "0603WAF1801T5E")
        (field (name "Manufacturer") "UNI-ROYAL(厚声)")
      )
      (libsource (lib "") (part "0603WAF1801T5E"))
    )
    (comp (ref "R10")
      (value "1.8kΩ")
      (fields
        (field (name "Manufacturer Part") "0603WAF1801T5E")
        (field (name "Manufacturer") "UNI-ROYAL(厚声)")
      )
      (libsource (lib "") (part "0603WAF1801T5E"))
    )
    (comp (ref "R11")
      (value "100kΩ")
      (fields
        (field (name "Manufacturer Part") "0603WAF1003T5E")
        (field (name "Manufacturer") "UNI-ROYAL(厚声)")
      )
      (libsource (lib "") (part "0603WAF1003T5E"))
    )
    (comp (ref "R12")
      (value "100kΩ")
      (fields
        (field (name "Manufacturer Part") "0603WAF1003T5E")
        (field (name "Manufacturer") "UNI-ROYAL(厚声)")
      )
      (libsource (lib "") (part "0603WAF1003T5E"))
    )
    (comp (ref "R13")
      (value "100kΩ")
      (fields
        (field (name "Manufacturer Part") "0603WAF1003T5E")
        (field (name "Manufacturer") "UNI-ROYAL(厚声)")
      )
      (libsource (lib "") (part "0603WAF1003T5E"))
    )
    (comp (ref "R14")
      (value "100kΩ")
      (fields
        (field (name "Manufacturer Part") "0603WAF1003T5E")
        (field (name "Manufacturer") "UNI-ROYAL(厚声)")
      )
      (libsource (lib "") (part "0603WAF1003T5E"))
    )
    (comp (ref "R15")
      (value "68Ω")
      (fields
        (field (name "Manufacturer Part") "25121WJ0680T4E")
        (field (name "Manufacturer") "UNI-ROYAL(厚声)")
      )
      (libsource (lib "") (part "25121WJ0680T4E"))
    )
    (comp (ref "SW1")
      (value "SKRPACE010")
      (fields (field (name "Manufacturer") "ALPSALPINE(阿尔卑斯阿尔派)"))
      (libsource (lib "") (part "SKRPACE010"))
    )
    (comp (ref "U1")
      (value "TPS54202DDCR")
      (fields (field (name "Manufacturer") "TI(德州仪器)"))
      (libsource (lib "") (part "TPS54202DDCR"))
    )
    (comp (ref "U2")
      (value "RP2040-ZERO")
      (fields
        (field (name "Manufacturer Part") "RP2040-Zero")
        (field (name "Manufacturer") "Waveshare(微雪电子)")
      )
      (libsource (lib "") (part "RP2040-ZERO"))
    )
  )
  (nets
    (net (code "1") (name "+5V") (class "Default")
      (node (ref "C10") (pin "2") (pinfunction "2_2") (pintype "unspecified"))
      (node (ref "C11") (pin "2") (pinfunction "2_2") (pintype "unspecified"))
      (node (ref "C12") (pin "2") (pinfunction "2_2") (pintype "unspecified"))
      (node (ref "C13") (pin "2") (pinfunction "2_2") (pintype "unspecified"))
      (node (ref "C14") (pin "2") (pinfunction "2_2") (pintype "unspecified"))
      (node (ref "C15") (pin "2") (pinfunction "2_2") (pintype "unspecified"))
      (node (ref "C16") (pin "2") (pinfunction "2_2") (pintype "unspecified"))
      (node (ref "C17") (pin "2") (pinfunction "2_2") (pintype "unspecified"))
      (node (ref "C18") (pin "2") (pinfunction "2_2") (pintype "unspecified"))
      (node (ref "C19") (pin "2") (pinfunction "2_2") (pintype "unspecified"))
      (node (ref "C20") (pin "2") (pinfunction "2_2") (pintype "unspecified"))
      (node (ref "C21") (pin "2") (pinfunction "2_2") (pintype "unspecified"))
      (node (ref "C22") (pin "2") (pinfunction "2_2") (pintype "unspecified"))
      (node (ref "C23") (pin "2") (pinfunction "2_2") (pintype "unspecified"))
      (node (ref "C24") (pin "2") (pinfunction "2_2") (pintype "unspecified"))
      (node (ref "C25") (pin "2") (pinfunction "2_2") (pintype "unspecified"))
      (node (ref "C26") (pin "2") (pinfunction "2_2") (pintype "unspecified"))
      (node (ref "C27") (pin "2") (pinfunction "2_2") (pintype "unspecified"))
      (node (ref "C28") (pin "2") (pinfunction "2_2") (pintype "unspecified"))
      (node (ref "C29") (pin "2") (pinfunction "2_2") (pintype "unspecified"))
      (node (ref "C30") (pin "2") (pinfunction "2_2") (pintype "unspecified"))
      (node (ref "C31") (pin "2") (pinfunction "2_2") (pintype "unspecified"))
      (node (ref "C32") (pin "2") (pinfunction "2_2") (pintype "unspecified"))
      (node (ref "C33") (pin "2") (pinfunction "2_2") (pintype "unspecified"))
      (node (ref "C34") (pin "2") (pinfunction "2_2") (pintype "unspecified"))
      (node (ref "C35") (pin "2") (pinfunction "2_2") (pintype "unspecified"))
      (node (ref "C36") (pin "2") (pinfunction "2_2") (pintype "unspecified"))
      (node (ref "C37") (pin "2") (pinfunction "2_2") (pintype "unspecified"))
      (node (ref "C38") (pin "2") (pinfunction "2_2") (pintype "unspecified"))
      (node (ref "C39") (pin "2") (pinfunction "2_2") (pintype "unspecified"))
      (node (ref "C40") (pin "2") (pinfunction "2_2") (pintype "unspecified"))
      (node (ref "C41") (pin "2") (pinfunction "2_2") (pintype "unspecified"))
      (node (ref "C42") (pin "2") (pinfunction "2_2") (pintype "unspecified"))
      (node (ref "C43") (pin "2") (pinfunction "2_2") (pintype "unspecified"))
      (node (ref "C44") (pin "2") (pinfunction "2_2") (pintype "unspecified"))
      (node (ref "C51") (pin "2") (pinfunction "2_2") (pintype "unspecified"))
      (node (ref "C52") (pin "2") (pinfunction "2_2") (pintype "unspecified"))
      (node (ref "C53") (pin "2") (pinfunction "2_2") (pintype "unspecified"))
      (node (ref "C54") (pin "2") (pinfunction "2_2") (pintype "unspecified"))
      (node (ref "C55") (pin "2") (pinfunction "2_2") (pintype "unspecified"))
      (node (ref "C56") (pin "2") (pinfunction "2_2") (pintype "unspecified"))
      (node (ref "C57") (pin "2") (pinfunction "2_2") (pintype "unspecified"))
      (node (ref "C58") (pin "2") (pinfunction "2_2") (pintype "unspecified"))
      (node (ref "C59") (pin "2") (pinfunction "2_2") (pintype "unspecified"))
      (node (ref "C6") (pin "2") (pinfunction "2_2") (pintype "unspecified"))
      (node (ref "C60") (pin "2") (pinfunction "2_2") (pintype "unspecified"))
      (node (ref "C61") (pin "2") (pinfunction "2_2") (pintype "unspecified"))
      (node (ref "C62") (pin "2") (pinfunction "2_2") (pintype "unspecified"))
      (node (ref "C63") (pin "2") (pinfunction "2_2") (pintype "unspecified"))
      (node (ref "C64") (pin "2") (pinfunction "2_2") (pintype "unspecified"))
      (node (ref "C65") (pin "2") (pinfunction "2_2") (pintype "unspecified"))
      (node (ref "C66") (pin "2") (pinfunction "2_2") (pintype "unspecified"))
      (node (ref "C67") (pin "2") (pinfunction "2_2") (pintype "unspecified"))
      (node (ref "C68") (pin "2") (pinfunction "2_2") (pintype "unspecified"))
      (node (ref "C69") (pin "2") (pinfunction "2_2") (pintype "unspecified"))
      (node (ref "C70") (pin "2") (pinfunction "2_2") (pintype "unspecified"))
      (node (ref "C71") (pin "2") (pinfunction "2_2") (pintype "unspecified"))
      (node (ref "C72") (pin "2") (pinfunction "2_2") (pintype "unspecified"))
      (node (ref "C73") (pin "2") (pinfunction "2_2") (pintype "unspecified"))
      (node (ref "C74") (pin "2") (pinfunction "2_2") (pintype "unspecified"))
      (node (ref "C75") (pin "2") (pinfunction "2_2") (pintype "unspecified"))
      (node (ref "C76") (pin "2") (pinfunction "2_2") (pintype "unspecified"))
      (node (ref "C77") (pin "2") (pinfunction "2_2") (pintype "unspecified"))
      (node (ref "C78") (pin "2") (pinfunction "2_2") (pintype "unspecified"))
      (node (ref "C79") (pin "2") (pinfunction "2_2") (pintype "unspecified"))
      (node (ref "C80") (pin "2") (pinfunction "2_2") (pintype "unspecified"))
      (node (ref "C81") (pin "2") (pinfunction "2_2") (pintype "unspecified"))
      (node (ref "C82") (pin "2") (pinfunction "2_2") (pintype "unspecified"))
      (node (ref "C83") (pin "2") (pinfunction "2_2") (pintype "unspecified"))
      (node (ref "C84") (pin "2") (pinfunction "2_2") (pintype "unspecified"))
      (node (ref "C85") (pin "2") (pinfunction "2_2") (pintype "unspecified"))
      (node (ref "C9") (pin "2") (pinfunction "2_2") (pintype "unspecified"))
      (node (ref "D2") (pin "1") (pinfunction "K_1") (pintype "unspecified"))
      (node (ref "LED1") (pin "2") (pinfunction "VDD_2") (pintype "unspecified"))
      (node (ref "LED10") (pin "2") (pinfunction "VDD_2") (pintype "unspecified"))
      (node (ref "LED11") (pin "2") (pinfunction "VDD_2") (pintype "unspecified"))
      (node (ref "LED12") (pin "2") (pinfunction "VDD_2") (pintype "unspecified"))
      (node (ref "LED13") (pin "2") (pinfunction "VDD_2") (pintype "unspecified"))
      (node (ref "LED14") (pin "2") (pinfunction "VDD_2") (pintype "unspecified"))
      (node (ref "LED15") (pin "2") (pinfunction "VDD_2") (pintype "unspecified"))
      (node (ref "LED16") (pin "2") (pinfunction "VDD_2") (pintype "unspecified"))
      (node (ref "LED17") (pin "2") (pinfunction "VDD_2") (pintype "unspecified"))
      (node (ref "LED18") (pin "2") (pinfunction "VDD_2") (pintype "unspecified"))
      (node (ref "LED19") (pin "2") (pinfunction "VDD_2") (pintype "unspecified"))
      (node (ref "LED2") (pin "2") (pinfunction "VDD_2") (pintype "unspecified"))
      (node (ref "LED20") (pin "2") (pinfunction "VDD_2") (pintype "unspecified"))
      (node (ref "LED21") (pin "2") (pinfunction "VDD_2") (pintype "unspecified"))
      (node (ref "LED22") (pin "2") (pinfunction "VDD_2") (pintype "unspecified"))
      (node (ref "LED23") (pin "2") (pinfunction "VDD_2") (pintype "unspecified"))
      (node (ref "LED24") (pin "2") (pinfunction "VDD_2") (pintype "unspecified"))
      (node (ref "LED25") (pin "2") (pinfunction "VDD_2") (pintype "unspecified"))
      (node (ref "LED26") (pin "2") (pinfunction "VDD_2") (pintype "unspecified"))
      (node (ref "LED27") (pin "2") (pinfunction "VDD_2") (pintype "unspecified"))
      (node (ref "LED28") (pin "2") (pinfunction "VDD_2") (pintype "unspecified"))
      (node (ref "LED29") (pin "2") (pinfunction "VDD_2") (pintype "unspecified"))
      (node (ref "LED3") (pin "2") (pinfunction "VDD_2") (pintype "unspecified"))
      (node (ref "LED30") (pin "2") (pinfunction "VDD_2") (pintype "unspecified"))
      (node (ref "LED31") (pin "2") (pinfunction "VDD_2") (pintype "unspecified"))
      (node (ref "LED32") (pin "2") (pinfunction "VDD_2") (pintype "unspecified"))
      (node (ref "LED33") (pin "2") (pinfunction "VDD_2") (pintype "unspecified"))
      (node (ref "LED34") (pin "2") (pinfunction "VDD_2") (pintype "unspecified"))
      (node (ref "LED35") (pin "2") (pinfunction "VDD_2") (pintype "unspecified"))
      (node (ref "LED36") (pin "2") (pinfunction "VDD_2") (pintype "unspecified"))
      (node (ref "LED4") (pin "2") (pinfunction "VDD_2") (pintype "unspecified"))
      (node (ref "LED43") (pin "2") (pinfunction "VDD_2") (pintype "unspecified"))
      (node (ref "LED44") (pin "2") (pinfunction "VDD_2") (pintype "unspecified"))
      (node (ref "LED45") (pin "2") (pinfunction "VDD_2") (pintype "unspecified"))
      (node (ref "LED46") (pin "2") (pinfunction "VDD_2") (pintype "unspecified"))
      (node (ref "LED47") (pin "2") (pinfunction "VDD_2") (pintype "unspecified"))
      (node (ref "LED48") (pin "2") (pinfunction "VDD_2") (pintype "unspecified"))
      (node (ref "LED49") (pin "2") (pinfunction "VDD_2") (pintype "unspecified"))
      (node (ref "LED5") (pin "2") (pinfunction "VDD_2") (pintype "unspecified"))
      (node (ref "LED50") (pin "2") (pinfunction "VDD_2") (pintype "unspecified"))
      (node (ref "LED51") (pin "2") (pinfunction "VDD_2") (pintype "unspecified"))
      (node (ref "LED52") (pin "2") (pinfunction "VDD_2") (pintype "unspecified"))
      (node (ref "LED53") (pin "2") (pinfunction "VDD_2") (pintype "unspecified"))
      (node (ref "LED54") (pin "2") (pinfunction "VDD_2") (pintype "unspecified"))
      (node (ref "LED55") (pin "2") (pinfunction "VDD_2") (pintype "unspecified"))
      (node (ref "LED56") (pin "2") (pinfunction "VDD_2") (pintype "unspecified"))
      (node (ref "LED57") (pin "2") (pinfunction "VDD_2") (pintype "unspecified"))
      (node (ref "LED58") (pin "2") (pinfunction "VDD_2") (pintype "unspecified"))
      (node (ref "LED59") (pin "2") (pinfunction "VDD_2") (pintype "unspecified"))
      (node (ref "LED6") (pin "2") (pinfunction "VDD_2") (pintype "unspecified"))
      (node (ref "LED60") (pin "2") (pinfunction "VDD_2") (pintype "unspecified"))
      (node (ref "LED61") (pin "2") (pinfunction "VDD_2") (pintype "unspecified"))
      (node (ref "LED62") (pin "2") (pinfunction "VDD_2") (pintype "unspecified"))
      (node (ref "LED63") (pin "2") (pinfunction "VDD_2") (pintype "unspecified"))
      (node (ref "LED64") (pin "2") (pinfunction "VDD_2") (pintype "unspecified"))
      (node (ref "LED65") (pin "2") (pinfunction "VDD_2") (pintype "unspecified"))
      (node (ref "LED66") (pin "2") (pinfunction "VDD_2") (pintype "unspecified"))
      (node (ref "LED67") (pin "2") (pinfunction "VDD_2") (pintype "unspecified"))
      (node (ref "LED68") (pin "2") (pinfunction "VDD_2") (pintype "unspecified"))
      (node (ref "LED69") (pin "2") (pinfunction "VDD_2") (pintype "unspecified"))
      (node (ref "LED7") (pin "2") (pinfunction "VDD_2") (pintype "unspecified"))
      (node (ref "LED70") (pin "2") (pinfunction "VDD_2") (pintype "unspecified"))
      (node (ref "LED71") (pin "2") (pinfunction "VDD_2") (pintype "unspecified"))
      (node (ref "LED72") (pin "2") (pinfunction "VDD_2") (pintype "unspecified"))
      (node (ref "LED73") (pin "2") (pinfunction "VDD_2") (pintype "unspecified"))
      (node (ref "LED74") (pin "2") (pinfunction "VDD_2") (pintype "unspecified"))
      (node (ref "LED75") (pin "2") (pinfunction "VDD_2") (pintype "unspecified"))
      (node (ref "LED76") (pin "2") (pinfunction "VDD_2") (pintype "unspecified"))
      (node (ref "LED77") (pin "2") (pinfunction "VDD_2") (pintype "unspecified"))
      (node (ref "LED78") (pin "2") (pinfunction "VDD_2") (pintype "unspecified"))
      (node (ref "LED8") (pin "2") (pinfunction "VDD_2") (pintype "unspecified"))
      (node (ref "LED9") (pin "2") (pinfunction "VDD_2") (pintype "unspecified"))
      (node (ref "U2") (pin "23") (pinfunction "5V_23") (pintype "unspecified"))
    )
    (net (code "2") (name "3V3") (class "Default")
      (node (ref "R11") (pin "2") (pinfunction "2_2") (pintype "input"))
      (node (ref "R13") (pin "2") (pinfunction "2_2") (pintype "input"))
      (node (ref "U2") (pin "21") (pinfunction "3V3_21") (pintype "unspecified"))
    )
    (net (code "3") (name "GND") (class "Default")
      (node (ref "C1") (pin "1") (pinfunction "1_1") (pintype "unspecified"))
      (node (ref "C10") (pin "1") (pinfunction "1_1") (pintype "unspecified"))
      (node (ref "C11") (pin "1") (pinfunction "1_1") (pintype "unspecified"))
      (node (ref "C12") (pin "1") (pinfunction "1_1") (pintype "unspecified"))
      (node (ref "C13") (pin "1") (pinfunction "1_1") (pintype "unspecified"))
      (node (ref "C14") (pin "1") (pinfunction "1_1") (pintype "unspecified"))
      (node (ref "C15") (pin "1") (pinfunction "1_1") (pintype "unspecified"))
      (node (ref "C16") (pin "1") (pinfunction "1_1") (pintype "unspecified"))
      (node (ref "C17") (pin "1") (pinfunction "1_1") (pintype "unspecified"))
      (node (ref "C18") (pin "1") (pinfunction "1_1") (pintype "unspecified"))
      (node (ref "C19") (pin "1") (pinfunction "1_1") (pintype "unspecified"))
      (node (ref "C20") (pin "1") (pinfunction "1_1") (pintype "unspecified"))
      (node (ref "C21") (pin "1") (pinfunction "1_1") (pintype "unspecified"))
      (node (ref "C22") (pin "1") (pinfunction "1_1") (pintype "unspecified"))
      (node (ref "C23") (pin "1") (pinfunction "1_1") (pintype "unspecified"))
      (node (ref "C24") (pin "1") (pinfunction "1_1") (pintype "unspecified"))
      (node (ref "C25") (pin "1") (pinfunction "1_1") (pintype "unspecified"))
      (node (ref "C26") (pin "1") (pinfunction "1_1") (pintype "unspecified"))
      (node (ref "C27") (pin "1") (pinfunction "1_1") (pintype "unspecified"))
      (node (ref "C28") (pin "1") (pinfunction "1_1") (pintype "unspecified"))
      (node (ref "C29") (pin "1") (pinfunction "1_1") (pintype "unspecified"))
      (node (ref "C30") (pin "1") (pinfunction "1_1") (pintype "unspecified"))
      (node (ref "C31") (pin "1") (pinfunction "1_1") (pintype "unspecified"))
      (node (ref "C32") (pin "1") (pinfunction "1_1") (pintype "unspecified"))
      (node (ref "C33") (pin "1") (pinfunction "1_1") (pintype "unspecified"))
      (node (ref "C34") (pin "1") (pinfunction "1_1") (pintype "unspecified"))
      (node (ref "C35") (pin "1") (pinfunction "1_1") (pintype "unspecified"))
      (node (ref "C36") (pin "1") (pinfunction "1_1") (pintype "unspecified"))
      (node (ref "C37") (pin "1") (pinfunction "1_1") (pintype "unspecified"))
      (node (ref "C38") (pin "1") (pinfunction "1_1") (pintype "unspecified"))
      (node (ref "C39") (pin "1") (pinfunction "1_1") (pintype "unspecified"))
      (node (ref "C4") (pin "1") (pinfunction "1_1") (pintype "unspecified"))
      (node (ref "C40") (pin "1") (pinfunction "1_1") (pintype "unspecified"))
      (node (ref "C41") (pin "1") (pinfunction "1_1") (pintype "unspecified"))
      (node (ref "C42") (pin "1") (pinfunction "1_1") (pintype "unspecified"))
      (node (ref "C43") (pin "1") (pinfunction "1_1") (pintype "unspecified"))
      (node (ref "C44") (pin "1") (pinfunction "1_1") (pintype "unspecified"))
      (node (ref "C47") (pin "1") (pinfunction "1_1") (pintype "input"))
      (node (ref "C48") (pin "1") (pinfunction "1_1") (pintype "input"))
      (node (ref "C49") (pin "2") (pinfunction "2_2") (pintype "unspecified"))
      (node (ref "C5") (pin "1") (pinfunction "1_1") (pintype "unspecified"))
      (node (ref "C50") (pin "2") (pinfunction "2_2") (pintype "unspecified"))
      (node (ref "C51") (pin "1") (pinfunction "1_1") (pintype "unspecified"))
      (node (ref "C52") (pin "1") (pinfunction "1_1") (pintype "unspecified"))
      (node (ref "C53") (pin "1") (pinfunction "1_1") (pintype "unspecified"))
      (node (ref "C54") (pin "1") (pinfunction "1_1") (pintype "unspecified"))
      (node (ref "C55") (pin "1") (pinfunction "1_1") (pintype "unspecified"))
      (node (ref "C56") (pin "1") (pinfunction "1_1") (pintype "unspecified"))
      (node (ref "C57") (pin "1") (pinfunction "1_1") (pintype "unspecified"))
      (node (ref "C58") (pin "1") (pinfunction "1_1") (pintype "unspecified"))
      (node (ref "C59") (pin "1") (pinfunction "1_1") (pintype "unspecified"))
      (node (ref "C6") (pin "1") (pinfunction "1_1") (pintype "unspecified"))
      (node (ref "C60") (pin "1") (pinfunction "1_1") (pintype "unspecified"))
      (node (ref "C61") (pin "1") (pinfunction "1_1") (pintype "unspecified"))
      (node (ref "C62") (pin "1") (pinfunction "1_1") (pintype "unspecified"))
      (node (ref "C63") (pin "1") (pinfunction "1_1") (pintype "unspecified"))
      (node (ref "C64") (pin "1") (pinfunction "1_1") (pintype "unspecified"))
      (node (ref "C65") (pin "1") (pinfunction "1_1") (pintype "unspecified"))
      (node (ref "C66") (pin "1") (pinfunction "1_1") (pintype "unspecified"))
      (node (ref "C67") (pin "1") (pinfunction "1_1") (pintype "unspecified"))
      (node (ref "C68") (pin "1") (pinfunction "1_1") (pintype "unspecified"))
      (node (ref "C69") (pin "1") (pinfunction "1_1") (pintype "unspecified"))
      (node (ref "C7") (pin "1") (pinfunction "1_1") (pintype "input"))
      (node (ref "C70") (pin "1") (pinfunction "1_1") (pintype "unspecified"))
      (node (ref "C71") (pin "1") (pinfunction "1_1") (pintype "unspecified"))
      (node (ref "C72") (pin "1") (pinfunction "1_1") (pintype "unspecified"))
      (node (ref "C73") (pin "1") (pinfunction "1_1") (pintype "unspecified"))
      (node (ref "C74") (pin "1") (pinfunction "1_1") (pintype "unspecified"))
      (node (ref "C75") (pin "1") (pinfunction "1_1") (pintype "unspecified"))
      (node (ref "C76") (pin "1") (pinfunction "1_1") (pintype "unspecified"))
      (node (ref "C77") (pin "1") (pinfunction "1_1") (pintype "unspecified"))
      (node (ref "C78") (pin "1") (pinfunction "1_1") (pintype "unspecified"))
      (node (ref "C79") (pin "1") (pinfunction "1_1") (pintype "unspecified"))
      (node (ref "C8") (pin "1") (pinfunction "1_1") (pintype "input"))
      (node (ref "C80") (pin "1") (pinfunction "1_1") (pintype "unspecified"))
      (node (ref "C81") (pin "1") (pinfunction "1_1") (pintype "unspecified"))
      (node (ref "C82") (pin "1") (pinfunction "1_1") (pintype "unspecified"))
      (node (ref "C83") (pin "1") (pinfunction "1_1") (pintype "unspecified"))
      (node (ref "C84") (pin "1") (pinfunction "1_1") (pintype "unspecified"))
      (node (ref "C85") (pin "1") (pinfunction "1_1") (pintype "unspecified"))
      (node (ref "C86") (pin "2") (pinfunction "2_2") (pintype "unspecified"))
      (node (ref "C9") (pin "1") (pinfunction "1_1") (pintype "unspecified"))
      (node (ref "LED1") (pin "4") (pinfunction "VSS_4") (pintype "unspecified"))
      (node (ref "LED10") (pin "4") (pinfunction "VSS_4") (pintype "unspecified"))
      (node (ref "LED11") (pin "4") (pinfunction "VSS_4") (pintype "unspecified"))
      (node (ref "LED12") (pin "4") (pinfunction "VSS_4") (pintype "unspecified"))
      (node (ref "LED13") (pin "4") (pinfunction "VSS_4") (pintype "unspecified"))
      (node (ref "LED14") (pin "4") (pinfunction "VSS_4") (pintype "unspecified"))
      (node (ref "LED15") (pin "4") (pinfunction "VSS_4") (pintype "unspecified"))
      (node (ref "LED16") (pin "4") (pinfunction "VSS_4") (pintype "unspecified"))
      (node (ref "LED17") (pin "4") (pinfunction "VSS_4") (pintype "unspecified"))
      (node (ref "LED18") (pin "4") (pinfunction "VSS_4") (pintype "unspecified"))
      (node (ref "LED19") (pin "4") (pinfunction "VSS_4") (pintype "unspecified"))
      (node (ref "LED2") (pin "4") (pinfunction "VSS_4") (pintype "unspecified"))
      (node (ref "LED20") (pin "4") (pinfunction "VSS_4") (pintype "unspecified"))
      (node (ref "LED21") (pin "4") (pinfunction "VSS_4") (pintype "unspecified"))
      (node (ref "LED22") (pin "4") (pinfunction "VSS_4") (pintype "unspecified"))
      (node (ref "LED23") (pin "4") (pinfunction "VSS_4") (pintype "unspecified"))
      (node (ref "LED24") (pin "4") (pinfunction "VSS_4") (pintype "unspecified"))
      (node (ref "LED25") (pin "4") (pinfunction "VSS_4") (pintype "unspecified"))
      (node (ref "LED26") (pin "4") (pinfunction "VSS_4") (pintype "unspecified"))
      (node (ref "LED27") (pin "4") (pinfunction "VSS_4") (pintype "unspecified"))
      (node (ref "LED28") (pin "4") (pinfunction "VSS_4") (pintype "unspecified"))
      (node (ref "LED29") (pin "4") (pinfunction "VSS_4") (pintype "unspecified"))
      (node (ref "LED3") (pin "4") (pinfunction "VSS_4") (pintype "unspecified"))
      (node (ref "LED30") (pin "4") (pinfunction "VSS_4") (pintype "unspecified"))
      (node (ref "LED31") (pin "4") (pinfunction "VSS_4") (pintype "unspecified"))
      (node (ref "LED32") (pin "4") (pinfunction "VSS_4") (pintype "unspecified"))
      (node (ref "LED33") (pin "4") (pinfunction "VSS_4") (pintype "unspecified"))
      (node (ref "LED34") (pin "4") (pinfunction "VSS_4") (pintype "unspecified"))
      (node (ref "LED35") (pin "4") (pinfunction "VSS_4") (pintype "unspecified"))
      (node (ref "LED36") (pin "4") (pinfunction "VSS_4") (pintype "unspecified"))
      (node (ref "LED4") (pin "4") (pinfunction "VSS_4") (pintype "unspecified"))
      (node (ref "LED43") (pin "4") (pinfunction "VSS_4") (pintype "unspecified"))
      (node (ref "LED44") (pin "4") (pinfunction "VSS_4") (pintype "unspecified"))
      (node (ref "LED45") (pin "4") (pinfunction "VSS_4") (pintype "unspecified"))
      (node (ref "LED46") (pin "4") (pinfunction "VSS_4") (pintype "unspecified"))
      (node (ref "LED47") (pin "4") (pinfunction "VSS_4") (pintype "unspecified"))
      (node (ref "LED48") (pin "4") (pinfunction "VSS_4") (pintype "unspecified"))
      (node (ref "LED49") (pin "4") (pinfunction "VSS_4") (pintype "unspecified"))
      (node (ref "LED5") (pin "4") (pinfunction "VSS_4") (pintype "unspecified"))
      (node (ref "LED50") (pin "4") (pinfunction "VSS_4") (pintype "unspecified"))
      (node (ref "LED51") (pin "4") (pinfunction "VSS_4") (pintype "unspecified"))
      (node (ref "LED52") (pin "4") (pinfunction "VSS_4") (pintype "unspecified"))
      (node (ref "LED53") (pin "4") (pinfunction "VSS_4") (pintype "unspecified"))
      (node (ref "LED54") (pin "4") (pinfunction "VSS_4") (pintype "unspecified"))
      (node (ref "LED55") (pin "4") (pinfunction "VSS_4") (pintype "unspecified"))
      (node (ref "LED56") (pin "4") (pinfunction "VSS_4") (pintype "unspecified"))
      (node (ref "LED57") (pin "4") (pinfunction "VSS_4") (pintype "unspecified"))
      (node (ref "LED58") (pin "4") (pinfunction "VSS_4") (pintype "unspecified"))
      (node (ref "LED59") (pin "4") (pinfunction "VSS_4") (pintype "unspecified"))
      (node (ref "LED6") (pin "4") (pinfunction "VSS_4") (pintype "unspecified"))
      (node (ref "LED60") (pin "4") (pinfunction "VSS_4") (pintype "unspecified"))
      (node (ref "LED61") (pin "4") (pinfunction "VSS_4") (pintype "unspecified"))
      (node (ref "LED62") (pin "4") (pinfunction "VSS_4") (pintype "unspecified"))
      (node (ref "LED63") (pin "4") (pinfunction "VSS_4") (pintype "unspecified"))
      (node (ref "LED64") (pin "4") (pinfunction "VSS_4") (pintype "unspecified"))
      (node (ref "LED65") (pin "4") (pinfunction "VSS_4") (pintype "unspecified"))
      (node (ref "LED66") (pin "4") (pinfunction "VSS_4") (pintype "unspecified"))
      (node (ref "LED67") (pin "4") (pinfunction "VSS_4") (pintype "unspecified"))
      (node (ref "LED68") (pin "4") (pinfunction "VSS_4") (pintype "unspecified"))
      (node (ref "LED69") (pin "4") (pinfunction "VSS_4") (pintype "unspecified"))
      (node (ref "LED7") (pin "4") (pinfunction "VSS_4") (pintype "unspecified"))
      (node (ref "LED70") (pin "4") (pinfunction "VSS_4") (pintype "unspecified"))
      (node (ref "LED71") (pin "4") (pinfunction "VSS_4") (pintype "unspecified"))
      (node (ref "LED72") (pin "4") (pinfunction "VSS_4") (pintype "unspecified"))
      (node (ref "LED73") (pin "4") (pinfunction "VSS_4") (pintype "unspecified"))
      (node (ref "LED74") (pin "4") (pinfunction "VSS_4") (pintype "unspecified"))
      (node (ref "LED75") (pin "4") (pinfunction "VSS_4") (pintype "unspecified"))
      (node (ref "LED76") (pin "4") (pinfunction "VSS_4") (pintype "unspecified"))
      (node (ref "LED77") (pin "4") (pinfunction "VSS_4") (pintype "unspecified"))
      (node (ref "LED78") (pin "4") (pinfunction "VSS_4") (pintype "unspecified"))
      (node (ref "LED8") (pin "4") (pinfunction "VSS_4") (pintype "unspecified"))
      (node (ref "LED9") (pin "4") (pinfunction "VSS_4") (pintype "unspecified"))
      (node (ref "P1") (pin "1") (pinfunction "1_1") (pintype "unspecified"))
      (node (ref "P4") (pin "1") (pinfunction "1_1") (pintype "unspecified"))
      (node (ref "P5") (pin "1") (pinfunction "1_1") (pintype "unspecified"))
      (node (ref "R10") (pin "1") (pinfunction "1_1") (pintype "input"))
      (node (ref "R12") (pin "1") (pinfunction "1_1") (pintype "input"))
      (node (ref "R14") (pin "1") (pinfunction "1_1") (pintype "input"))
      (node (ref "R2") (pin "1") (pinfunction "1_1") (pintype "input"))
      (node (ref "R9") (pin "1") (pinfunction "1_1") (pintype "input"))
      (node (ref "SW1") (pin "3") (pinfunction "3_3") (pintype "unspecified"))
      (node (ref "SW1") (pin "4") (pinfunction "4_4") (pintype "unspecified"))
      (node (ref "U1") (pin "1") (pinfunction "GND_1") (pintype "unspecified"))
      (node (ref "U2") (pin "22") (pinfunction "GND_22") (pintype "unspecified"))
    )
    (net (code "4") (name "LEFT") (class "Default")
      (node (ref "LED1") (pin "1") (pinfunction "DIN_1") (pintype "unspecified"))
      (node (ref "U2") (pin "15") (pinfunction "GP14_15") (pintype "unspecified"))
    )
    (net (code "5") (name "Net-(C45-Pad1)") (class "Default")
      (node (ref "C45") (pin "1") (pinfunction "1_1") (pintype "input"))
      (node (ref "P2") (pin "2") (pinfunction "2_2") (pintype "unspecified"))
      (node (ref "R3") (pin "2") (pinfunction "2_2") (pintype "input"))
    )
    (net (code "6") (name "Net-(C45-Pad2)") (class "Default")
      (node (ref "C45") (pin "2") (pinfunction "2_2") (pintype "input"))
      (node (ref "C49") (pin "1") (pinfunction "1_1") (pintype "unspecified"))
      (node (ref "R5") (pin "1") (pinfunction "1_1") (pintype "input"))
    )
    (net (code "7") (name "Net-(C46-Pad1)") (class "Default")
      (node (ref "C46") (pin "1") (pinfunction "1_1") (pintype "input"))
      (node (ref "P3") (pin "1") (pinfunction "1_1") (pintype "unspecified"))
      (node (ref "R4") (pin "2") (pinfunction "2_2") (pintype "input"))
    )
    (net (code "8") (name "Net-(C46-Pad2)") (class "Default")
      (node (ref "C46") (pin "2") (pinfunction "2_2") (pintype "input"))
      (node (ref "C50") (pin "1") (pinfunction "1_1") (pintype "unspecified"))
      (node (ref "R6") (pin "1") (pinfunction "1_1") (pintype "input"))
    )
    (net (code "9") (name "Net-(D1-A)") (class "Default")
      (node (ref "D1") (pin "2") (pinfunction "A_2") (pintype "unspecified"))
      (node (ref "P1") (pin "2") (pinfunction "2_2") (pintype "unspecified"))
    )
    (net (code "10") (name "Net-(D1-K)") (class "Default")
      (node (ref "D1") (pin "1") (pinfunction "K_1") (pintype "unspecified"))
      (node (ref "R15") (pin "1") (pinfunction "1_1") (pintype "input"))
    )
    (net (code "11") (name "Net-(D2-A)") (class "Default")
      (node (ref "C3") (pin "2") (pinfunction "2_2") (pintype "unspecified"))
      (node (ref "C4") (pin "2") (pinfunction "2_2") (pintype "unspecified"))
      (node (ref "C5") (pin "2") (pinfunction "2_2") (pintype "unspecified"))
      (node (ref "D2") (pin "2") (pinfunction "A_2") (pintype "unspecified"))
      (node (ref "L1") (pin "2") (pinfunction "2_2") (pintype "unspecified"))
      (node (ref "R1") (pin "2") (pinfunction "2_2") (pintype "input"))
    )
    (net (code "12") (name "Net-(LED1-DOUT)") (class "Default")
      (node (ref "LED1") (pin "3") (pinfunction "DOUT_3") (pintype "unspecified"))
      (node (ref "LED2") (pin "1") (pinfunction "DIN_1") (pintype "unspecified"))
    )
    (net (code "13") (name "Net-(LED2-DOUT)") (class "Default")
      (node (ref "LED2") (pin "3") (pinfunction "DOUT_3") (pintype "unspecified"))
      (node (ref "LED3") (pin "1") (pinfunction "DIN_1") (pintype "unspecified"))
    )
    (net (code "14") (name "Net-(LED3-DOUT)") (class "Default")
      (node (ref "LED3") (pin "3") (pinfunction "DOUT_3") (pintype "unspecified"))
      (node (ref "LED4") (pin "1") (pinfunction "DIN_1") (pintype "unspecified"))
    )
    (net (code "15") (name "Net-(LED4-DOUT)") (class "Default")
      (node (ref "LED4") (pin "3") (pinfunction "DOUT_3") (pintype "unspecified"))
      (node (ref "LED5") (pin "1") (pinfunction "DIN_1") (pintype "unspecified"))
    )
    (net (code "16") (name "Net-(LED5-DOUT)") (class "Default")
      (node (ref "LED5") (pin "3") (pinfunction "DOUT_3") (pintype "unspecified"))
      (node (ref "LED6") (pin "1") (pinfunction "DIN_1") (pintype "unspecified"))
    )
    (net (code "17") (name "Net-(LED6-DOUT)") (class "Default")
      (node (ref "LED6") (pin "3") (pinfunction "DOUT_3") (pintype "unspecified"))
      (node (ref "LED7") (pin "1") (pinfunction "DIN_1") (pintype "unspecified"))
    )
    (net (code "18") (name "Net-(LED7-DOUT)") (class "Default")
      (node (ref "LED7") (pin "3") (pinfunction "DOUT_3") (pintype "unspecified"))
      (node (ref "LED8") (pin "1") (pinfunction "DIN_1") (pintype "unspecified"))
    )
    (net (code "19") (name "Net-(LED8-DOUT)") (class "Default")
      (node (ref "LED8") (pin "3") (pinfunction "DOUT_3") (pintype "unspecified"))
      (node (ref "LED9") (pin "1") (pinfunction "DIN_1") (pintype "unspecified"))
    )
    (net (code "20") (name "Net-(LED10-DIN)") (class "Default")
      (node (ref "LED10") (pin "1") (pinfunction "DIN_1") (pintype "unspecified"))
      (node (ref "LED9") (pin "3") (pinfunction "DOUT_3") (pintype "unspecified"))
    )
    (net (code "21") (name "Net-(LED10-DOUT)") (class "Default")
      (node (ref "LED10") (pin "3") (pinfunction "DOUT_3") (pintype "unspecified"))
      (node (ref "LED11") (pin "1") (pinfunction "DIN_1") (pintype "unspecified"))
    )
    (net (code "22") (name "Net-(LED11-DOUT)") (class "Default")
      (node (ref "LED11") (pin "3") (pinfunction "DOUT_3") (pintype "unspecified"))
      (node (ref "LED12") (pin "1") (pinfunction "DIN_1") (pintype "unspecified"))
    )
    (net (code "23") (name "Net-(LED12-DOUT)") (class "Default")
      (node (ref "LED12") (pin "3") (pinfunction "DOUT_3") (pintype "unspecified"))
      (node (ref "LED13") (pin "1") (pinfunction "DIN_1") (pintype "unspecified"))
    )
    (net (code "24") (name "Net-(LED13-DOUT)") (class "Default")
      (node (ref "LED13") (pin "3") (pinfunction "DOUT_3") (pintype "unspecified"))
      (node (ref "LED14") (pin "1") (pinfunction "DIN_1") (pintype "unspecified"))
    )
    (net (code "25") (name "Net-(LED14-DOUT)") (class "Default")
      (node (ref "LED14") (pin "3") (pinfunction "DOUT_3") (pintype "unspecified"))
      (node (ref "LED15") (pin "1") (pinfunction "DIN_1") (pintype "unspecified"))
    )
    (net (code "26") (name "Net-(LED15-DOUT)") (class "Default")
      (node (ref "LED15") (pin "3") (pinfunction "DOUT_3") (pintype "unspecified"))
      (node (ref "LED16") (pin "1") (pinfunction "DIN_1") (pintype "unspecified"))
    )
    (net (code "27") (name "Net-(LED16-DOUT)") (class "Default")
      (node (ref "LED16") (pin "3") (pinfunction "DOUT_3") (pintype "unspecified"))
      (node (ref "LED17") (pin "1") (pinfunction "DIN_1") (pintype "unspecified"))
    )
    (net (code "28") (name "Net-(LED17-DOUT)") (class "Default")
      (node (ref "LED17") (pin "3") (pinfunction "DOUT_3") (pintype "unspecified"))
      (node (ref "LED18") (pin "1") (pinfunction "DIN_1") (pintype "unspecified"))
    )
    (net (code "29") (name "Net-(LED18-DOUT)") (class "Default")
      (node (ref "LED18") (pin "3") (pinfunction "DOUT_3") (pintype "unspecified"))
      (node (ref "LED19") (pin "1") (pinfunction "DIN_1") (pintype "unspecified"))
    )
    (net (code "30") (name "Net-(LED19-DOUT)") (class "Default")
      (node (ref "LED19") (pin "3") (pinfunction "DOUT_3") (pintype "unspecified"))
      (node (ref "LED20") (pin "1") (pinfunction "DIN_1") (pintype "unspecified"))
    )
    (net (code "31") (name "Net-(LED20-DOUT)") (class "Default")
      (node (ref "LED20") (pin "3") (pinfunction "DOUT_3") (pintype "unspecified"))
      (node (ref "LED21") (pin "1") (pinfunction "DIN_1") (pintype "unspecified"))
    )
    (net (code "32") (name "Net-(LED21-DOUT)") (class "Default")
      (node (ref "LED21") (pin "3") (pinfunction "DOUT_3") (pintype "unspecified"))
      (node (ref "LED22") (pin "1") (pinfunction "DIN_1") (pintype "unspecified"))
    )
    (net (code "33") (name "Net-(LED22-DOUT)") (class "Default")
      (node (ref "LED22") (pin "3") (pinfunction "DOUT_3") (pintype "unspecified"))
      (node (ref "LED23") (pin "1") (pinfunction "DIN_1") (pintype "unspecified"))
    )
    (net (code "34") (name "Net-(LED23-DOUT)") (class "Default")
      (node (ref "LED23") (pin "3") (pinfunction "DOUT_3") (pintype "unspecified"))
      (node (ref "LED24") (pin "1") (pinfunction "DIN_1") (pintype "unspecified"))
    )
    (net (code "35") (name "Net-(LED24-DOUT)") (class "Default")
      (node (ref "LED24") (pin "3") (pinfunction "DOUT_3") (pintype "unspecified"))
      (node (ref "LED25") (pin "1") (pinfunction "DIN_1") (pintype "unspecified"))
    )
    (net (code "36") (name "Net-(LED25-DOUT)") (class "Default")
      (node (ref "LED25") (pin "3") (pinfunction "DOUT_3") (pintype "unspecified"))
      (node (ref "LED26") (pin "1") (pinfunction "DIN_1") (pintype "unspecified"))
    )
    (net (code "37") (name "Net-(LED26-DOUT)") (class "Default")
      (node (ref "LED26") (pin "3") (pinfunction "DOUT_3") (pintype "unspecified"))
      (node (ref "LED27") (pin "1") (pinfunction "DIN_1") (pintype "unspecified"))
    )
    (net (code "38") (name "Net-(LED27-DOUT)") (class "Default")
      (node (ref "LED27") (pin "3") (pinfunction "DOUT_3") (pintype "unspecified"))
      (node (ref "LED28") (pin "1") (pinfunction "DIN_1") (pintype "unspecified"))
    )
    (net (code "39") (name "Net-(LED28-DOUT)") (class "Default")
      (node (ref "LED28") (pin "3") (pinfunction "DOUT_3") (pintype "unspecified"))
      (node (ref "LED29") (pin "1") (pinfunction "DIN_1") (pintype "unspecified"))
    )
    (net (code "40") (name "Net-(LED29-DOUT)") (class "Default")
      (node (ref "LED29") (pin "3") (pinfunction "DOUT_3") (pintype "unspecified"))
      (node (ref "LED30") (pin "1") (pinfunction "DIN_1") (pintype "unspecified"))
    )
    (net (code "41") (name "Net-(LED30-DOUT)") (class "Default")
      (node (ref "LED30") (pin "3") (pinfunction "DOUT_3") (pintype "unspecified"))
      (node (ref "LED31") (pin "1") (pinfunction "DIN_1") (pintype "unspecified"))
    )
    (net (code "42") (name "Net-(LED31-DOUT)") (class "Default")
      (node (ref "LED31") (pin "3") (pinfunction "DOUT_3") (pintype "unspecified"))
      (node (ref "LED32") (pin "1") (pinfunction "DIN_1") (pintype "unspecified"))
    )
    (net (code "43") (name "Net-(LED32-DOUT)") (class "Default")
      (node (ref "LED32") (pin "3") (pinfunction "DOUT_3") (pintype "unspecified"))
      (node (ref "LED33") (pin "1") (pinfunction "DIN_1") (pintype "unspecified"))
    )
    (net (code "44") (name "Net-(LED33-DOUT)") (class "Default")
      (node (ref "LED33") (pin "3") (pinfunction "DOUT_3") (pintype "unspecified"))
      (node (ref "LED34") (pin "1") (pinfunction "DIN_1") (pintype "unspecified"))
    )
    (net (code "45") (name "Net-(LED34-DOUT)") (class "Default")
      (node (ref "LED34") (pin "3") (pinfunction "DOUT_3") (pintype "unspecified"))
      (node (ref "LED35") (pin "1") (pinfunction "DIN_1") (pintype "unspecified"))
    )
    (net (code "46") (name "Net-(LED35-DOUT)") (class "Default")
      (node (ref "LED35") (pin "3") (pinfunction "DOUT_3") (pintype "unspecified"))
      (node (ref "LED36") (pin "1") (pinfunction "DIN_1") (pintype "unspecified"))
    )
    (net (code "47") (name "Net-(LED43-DOUT)") (class "Default")
      (node (ref "LED43") (pin "3") (pinfunction "DOUT_3") (pintype "unspecified"))
      (node (ref "LED44") (pin "1") (pinfunction "DIN_1") (pintype "unspecified"))
    )
    (net (code "48") (name "Net-(LED44-DOUT)") (class "Default")
      (node (ref "LED44") (pin "3") (pinfunction "DOUT_3") (pintype "unspecified"))
      (node (ref "LED45") (pin "1") (pinfunction "DIN_1") (pintype "unspecified"))
    )
    (net (code "49") (name "Net-(LED45-DOUT)") (class "Default")
      (node (ref "LED45") (pin "3") (pinfunction "DOUT_3") (pintype "unspecified"))
      (node (ref "LED46") (pin "1") (pinfunction "DIN_1") (pintype "unspecified"))
    )
    (net (code "50") (name "Net-(LED46-DOUT)") (class "Default")
      (node (ref "LED46") (pin "3") (pinfunction "DOUT_3") (pintype "unspecified"))
      (node (ref "LED47") (pin "1") (pinfunction "DIN_1") (pintype "unspecified"))
    )
    (net (code "51") (name "Net-(LED47-DOUT)") (class "Default")
      (node (ref "LED47") (pin "3") (pinfunction "DOUT_3") (pintype "unspecified"))
      (node (ref "LED48") (pin "1") (pinfunction "DIN_1") (pintype "unspecified"))
    )
    (net (code "52") (name "Net-(LED48-DOUT)") (class "Default")
      (node (ref "LED48") (pin "3") (pinfunction "DOUT_3") (pintype "unspecified"))
      (node (ref "LED49") (pin "1") (pinfunction "DIN_1") (pintype "unspecified"))
    )
    (net (code "53") (name "Net-(LED49-DOUT)") (class "Default")
      (node (ref "LED49") (pin "3") (pinfunction "DOUT_3") (pintype "unspecified"))
      (node (ref "LED50") (pin "1") (pinfunction "DIN_1") (pintype "unspecified"))
    )
    (net (code "54") (name "Net-(LED50-DOUT)") (class "Default")
      (node (ref "LED50") (pin "3") (pinfunction "DOUT_3") (pintype "unspecified"))
      (node (ref "LED51") (pin "1") (pinfunction "DIN_1") (pintype "unspecified"))
    )
    (net (code "55") (name "Net-(LED51-DOUT)") (class "Default")
      (node (ref "LED51") (pin "3") (pinfunction "DOUT_3") (pintype "unspecified"))
      (node (ref "LED52") (pin "1") (pinfunction "DIN_1") (pintype "unspecified"))
    )
    (net (code "56") (name "Net-(LED52-DOUT)") (class "Default")
      (node (ref "LED52") (pin "3") (pinfunction "DOUT_3") (pintype "unspecified"))
      (node (ref "LED53") (pin "1") (pinfunction "DIN_1") (pintype "unspecified"))
    )
    (net (code "57") (name "Net-(LED53-DOUT)") (class "Default")
      (node (ref "LED53") (pin "3") (pinfunction "DOUT_3") (pintype "unspecified"))
      (node (ref "LED54") (pin "1") (pinfunction "DIN_1") (pintype "unspecified"))
    )
    (net (code "58") (name "Net-(LED54-DOUT)") (class "Default")
      (node (ref "LED54") (pin "3") (pinfunction "DOUT_3") (pintype "unspecified"))
      (node (ref "LED55") (pin "1") (pinfunction "DIN_1") (pintype "unspecified"))
    )
    (net (code "59") (name "Net-(LED55-DOUT)") (class "Default")
      (node (ref "LED55") (pin "3") (pinfunction "DOUT_3") (pintype "unspecified"))
      (node (ref "LED56") (pin "1") (pinfunction "DIN_1") (pintype "unspecified"))
    )
    (net (code "60") (name "Net-(LED56-DOUT)") (class "Default")
      (node (ref "LED56") (pin "3") (pinfunction "DOUT_3") (pintype "unspecified"))
      (node (ref "LED57") (pin "1") (pinfunction "DIN_1") (pintype "unspecified"))
    )
    (net (code "61") (name "Net-(LED57-DOUT)") (class "Default")
      (node (ref "LED57") (pin "3") (pinfunction "DOUT_3") (pintype "unspecified"))
      (node (ref "LED58") (pin "1") (pinfunction "DIN_1") (pintype "unspecified"))
    )
    (net (code "62") (name "Net-(LED58-DOUT)") (class "Default")
      (node (ref "LED58") (pin "3") (pinfunction "DOUT_3") (pintype "unspecified"))
      (node (ref "LED59") (pin "1") (pinfunction "DIN_1") (pintype "unspecified"))
    )
    (net (code "63") (name "Net-(LED59-DOUT)") (class "Default")
      (node (ref "LED59") (pin "3") (pinfunction "DOUT_3") (pintype "unspecified"))
      (node (ref "LED60") (pin "1") (pinfunction "DIN_1") (pintype "unspecified"))
    )
    (net (code "64") (name "Net-(LED60-DOUT)") (class "Default")
      (node (ref "LED60") (pin "3") (pinfunction "DOUT_3") (pintype "unspecified"))
      (node (ref "LED61") (pin "1") (pinfunction "DIN_1") (pintype "unspecified"))
    )
    (net (code "65") (name "Net-(LED61-DOUT)") (class "Default")
      (node (ref "LED61") (pin "3") (pinfunction "DOUT_3") (pintype "unspecified"))
      (node (ref "LED62") (pin "1") (pinfunction "DIN_1") (pintype "unspecified"))
    )
    (net (code "66") (name "Net-(LED62-DOUT)") (class "Default")
      (node (ref "LED62") (pin "3") (pinfunction "DOUT_3") (pintype "unspecified"))
      (node (ref "LED63") (pin "1") (pinfunction "DIN_1") (pintype "unspecified"))
    )
    (net (code "67") (name "Net-(LED63-DOUT)") (class "Default")
      (node (ref "LED63") (pin "3") (pinfunction "DOUT_3") (pintype "unspecified"))
      (node (ref "LED64") (pin "1") (pinfunction "DIN_1") (pintype "unspecified"))
    )
    (net (code "68") (name "Net-(LED64-DOUT)") (class "Default")
      (node (ref "LED64") (pin "3") (pinfunction "DOUT_3") (pintype "unspecified"))
      (node (ref "LED65") (pin "1") (pinfunction "DIN_1") (pintype "unspecified"))
    )
    (net (code "69") (name "Net-(LED65-DOUT)") (class "Default")
      (node (ref "LED65") (pin "3") (pinfunction "DOUT_3") (pintype "unspecified"))
      (node (ref "LED66") (pin "1") (pinfunction "DIN_1") (pintype "unspecified"))
    )
    (net (code "70") (name "Net-(LED66-DOUT)") (class "Default")
      (node (ref "LED66") (pin "3") (pinfunction "DOUT_3") (pintype "unspecified"))
      (node (ref "LED67") (pin "1") (pinfunction "DIN_1") (pintype "unspecified"))
    )
    (net (code "71") (name "Net-(LED67-DOUT)") (class "Default")
      (node (ref "LED67") (pin "3") (pinfunction "DOUT_3") (pintype "unspecified"))
      (node (ref "LED68") (pin "1") (pinfunction "DIN_1") (pintype "unspecified"))
    )
    (net (code "72") (name "Net-(LED68-DOUT)") (class "Default")
      (node (ref "LED68") (pin "3") (pinfunction "DOUT_3") (pintype "unspecified"))
      (node (ref "LED69") (pin "1") (pinfunction "DIN_1") (pintype "unspecified"))
    )
    (net (code "73") (name "Net-(LED69-DOUT)") (class "Default")
      (node (ref "LED69") (pin "3") (pinfunction "DOUT_3") (pintype "unspecified"))
      (node (ref "LED70") (pin "1") (pinfunction "DIN_1") (pintype "unspecified"))
    )
    (net (code "74") (name "Net-(LED70-DOUT)") (class "Default")
      (node (ref "LED70") (pin "3") (pinfunction "DOUT_3") (pintype "unspecified"))
      (node (ref "LED71") (pin "1") (pinfunction "DIN_1") (pintype "unspecified"))
    )
    (net (code "75") (name "Net-(LED71-DOUT)") (class "Default")
      (node (ref "LED71") (pin "3") (pinfunction "DOUT_3") (pintype "unspecified"))
      (node (ref "LED72") (pin "1") (pinfunction "DIN_1") (pintype "unspecified"))
    )
    (net (code "76") (name "Net-(LED72-DOUT)") (class "Default")
      (node (ref "LED72") (pin "3") (pinfunction "DOUT_3") (pintype "unspecified"))
      (node (ref "LED73") (pin "1") (pinfunction "DIN_1") (pintype "unspecified"))
    )
    (net (code "77") (name "Net-(LED73-DOUT)") (class "Default")
      (node (ref "LED73") (pin "3") (pinfunction "DOUT_3") (pintype "unspecified"))
      (node (ref "LED74") (pin "1") (pinfunction "DIN_1") (pintype "unspecified"))
    )
    (net (code "78") (name "Net-(LED74-DOUT)") (class "Default")
      (node (ref "LED74") (pin "3") (pinfunction "DOUT_3") (pintype "unspecified"))
      (node (ref "LED75") (pin "1") (pinfunction "DIN_1") (pintype "unspecified"))
    )
    (net (code "79") (name "Net-(LED75-DOUT)") (class "Default")
      (node (ref "LED75") (pin "3") (pinfunction "DOUT_3") (pintype "unspecified"))
      (node (ref "LED76") (pin "1") (pinfunction "DIN_1") (pintype "unspecified"))
    )
    (net (code "80") (name "Net-(LED76-DOUT)") (class "Default")
      (node (ref "LED76") (pin "3") (pinfunction "DOUT_3") (pintype "unspecified"))
      (node (ref "LED77") (pin "1") (pinfunction "DIN_1") (pintype "unspecified"))
    )
    (net (code "81") (name "Net-(LED77-DOUT)") (class "Default")
      (node (ref "LED77") (pin "3") (pinfunction "DOUT_3") (pintype "unspecified"))
      (node (ref "LED78") (pin "1") (pinfunction "DIN_1") (pintype "unspecified"))
    )
    (net (code "82") (name "Net-(P2-Pad1)") (class "Default")
      (node (ref "P2") (pin "1") (pinfunction "1_1") (pintype "unspecified"))
      (node (ref "R3") (pin "1") (pinfunction "1_1") (pintype "input"))
    )
    (net (code "83") (name "Net-(P3-Pad2)") (class "Default")
      (node (ref "P3") (pin "2") (pinfunction "2_2") (pintype "unspecified"))
      (node (ref "R4") (pin "1") (pinfunction "1_1") (pintype "input"))
    )
    (net (code "84") (name "Net-(P4-Pad2)") (class "Default")
      (node (ref "P4") (pin "2") (pinfunction "2_2") (pintype "unspecified"))
      (node (ref "R7") (pin "2") (pinfunction "2_2") (pintype "input"))
    )
    (net (code "85") (name "Net-(P5-Pad2)") (class "Default")
      (node (ref "P5") (pin "2") (pinfunction "2_2") (pintype "unspecified"))
      (node (ref "R8") (pin "2") (pinfunction "2_2") (pintype "input"))
    )
    (net (code "86") (name "Net-(U1-BOOT)") (class "Default")
      (node (ref "C2") (pin "1") (pinfunction "1_1") (pintype "unspecified"))
      (node (ref "U1") (pin "6") (pinfunction "BOOT_6") (pintype "unspecified"))
    )
    (net (code "87") (name "Net-(U1-FB)") (class "Default")
      (node (ref "C3") (pin "1") (pinfunction "1_1") (pintype "unspecified"))
      (node (ref "R1") (pin "1") (pinfunction "1_1") (pintype "input"))
      (node (ref "R2") (pin "2") (pinfunction "2_2") (pintype "input"))
      (node (ref "U1") (pin "4") (pinfunction "FB_4") (pintype "unspecified"))
    )
    (net (code "88") (name "Net-(U1-SW)") (class "Default")
      (node (ref "C2") (pin "2") (pinfunction "2_2") (pintype "unspecified"))
      (node (ref "L1") (pin "1") (pinfunction "1_1") (pintype "unspecified"))
      (node (ref "U1") (pin "2") (pinfunction "SW_2") (pintype "unspecified"))
    )
    (net (code "89") (name "Net-(U1-VIN)") (class "Default")
      (node (ref "C1") (pin "2") (pinfunction "2_2") (pintype "unspecified"))
      (node (ref "C86") (pin "1") (pinfunction "1_1") (pintype "unspecified"))
      (node (ref "R15") (pin "2") (pinfunction "2_2") (pintype "input"))
      (node (ref "U1") (pin "3") (pinfunction "VIN_3") (pintype "unspecified"))
    )
    (net (code "90") (name "Net-(U2-GP2)") (class "Default")
      (node (ref "C47") (pin "2") (pinfunction "2_2") (pintype "input"))
      (node (ref "R7") (pin "1") (pinfunction "1_1") (pintype "input"))
      (node (ref "R9") (pin "2") (pinfunction "2_2") (pintype "input"))
      (node (ref "U2") (pin "3") (pinfunction "GP2_3") (pintype "unspecified"))
    )
    (net (code "91") (name "Net-(U2-GP3)") (class "Default")
      (node (ref "C48") (pin "2") (pinfunction "2_2") (pintype "input"))
      (node (ref "R10") (pin "2") (pinfunction "2_2") (pintype "input"))
      (node (ref "R8") (pin "1") (pinfunction "1_1") (pintype "input"))
      (node (ref "U2") (pin "4") (pinfunction "GP3_4") (pintype "unspecified"))
    )
    (net (code "92") (name "Net-(U2-GP8)") (class "Default")
      (node (ref "SW1") (pin "1") (pinfunction "1_1") (pintype "unspecified"))
      (node (ref "SW1") (pin "2") (pinfunction "2_2") (pintype "unspecified"))
      (node (ref "U2") (pin "9") (pinfunction "GP8_9") (pintype "unspecified"))
    )
    (net (code "93") (name "Net-(U2-GP27)") (class "Default")
      (node (ref "C7") (pin "2") (pinfunction "2_2") (pintype "input"))
      (node (ref "R13") (pin "1") (pinfunction "1_1") (pintype "input"))
      (node (ref "R14") (pin "2") (pinfunction "2_2") (pintype "input"))
      (node (ref "R6") (pin "2") (pinfunction "2_2") (pintype "input"))
      (node (ref "U2") (pin "18") (pinfunction "GP27_18") (pintype "unspecified"))
    )
    (net (code "94") (name "Net-(U2-GP28)") (class "Default")
      (node (ref "C8") (pin "2") (pinfunction "2_2") (pintype "input"))
      (node (ref "R11") (pin "1") (pinfunction "1_1") (pintype "input"))
      (node (ref "R12") (pin "2") (pinfunction "2_2") (pintype "input"))
      (node (ref "R5") (pin "2") (pinfunction "2_2") (pintype "input"))
      (node (ref "U2") (pin "19") (pinfunction "GP28_19") (pintype "unspecified"))
    )
    (net (code "95") (name "RIGHT") (class "Default")
      (node (ref "LED43") (pin "1") (pinfunction "DIN_1") (pintype "unspecified"))
      (node (ref "U2") (pin "16") (pinfunction "GP15_16") (pintype "unspecified"))
    )
    (net (code "96") (name "unconnected-(LED36-DOUT-Pad3)") (class "Default")
      (node (ref "LED36") (pin "3") (pinfunction "DOUT_3") (pintype "unspecified+no_connect"))
    )
    (net (code "97") (name "unconnected-(LED78-DOUT-Pad3)") (class "Default")
      (node (ref "LED78") (pin "3") (pinfunction "DOUT_3") (pintype "unspecified+no_connect"))
    )
    (net (code "98") (name "unconnected-(U1-EN-Pad5)") (class "Default")
      (node (ref "U1") (pin "5") (pinfunction "EN_5") (pintype "unspecified+no_connect"))
    )
    (net (code "99") (name "unconnected-(U2-GP0-Pad1)") (class "Default")
      (node (ref "U2") (pin "1") (pinfunction "GP0_1") (pintype "unspecified+no_connect"))
    )
    (net (code "100") (name "unconnected-(U2-GP1-Pad2)") (class "Default")
      (node (ref "U2") (pin "2") (pinfunction "GP1_2") (pintype "unspecified+no_connect"))
    )
    (net (code "101") (name "unconnected-(U2-GP4-Pad5)") (class "Default")
      (node (ref "U2") (pin "5") (pinfunction "GP4_5") (pintype "unspecified+no_connect"))
    )
    (net (code "102") (name "unconnected-(U2-GP5-Pad6)") (class "Default")
      (node (ref "U2") (pin "6") (pinfunction "GP5_6") (pintype "unspecified+no_connect"))
    )
    (net (code "103") (name "unconnected-(U2-GP6-Pad7)") (class "Default")
      (node (ref "U2") (pin "7") (pinfunction "GP6_7") (pintype "unspecified+no_connect"))
    )
    (net (code "104") (name "unconnected-(U2-GP7-Pad8)") (class "Default")
      (node (ref "U2") (pin "8") (pinfunction "GP7_8") (pintype "unspecified+no_connect"))
    )
    (net (code "105") (name "unconnected-(U2-GP9-Pad10)") (class "Default")
      (node (ref "U2") (pin "10") (pinfunction "GP9_10") (pintype "unspecified+no_connect"))
    )
    (net (code "106") (name "unconnected-(U2-GP10-Pad11)") (class "Default")
      (node (ref "U2") (pin "11") (pinfunction "GP10_11") (pintype "unspecified+no_connect"))
    )
    (net (code "107") (name "unconnected-(U2-GP11-Pad12)") (class "Default")
      (node (ref "U2") (pin "12") (pinfunction "GP11_12") (pintype "unspecified+no_connect"))
    )
    (net (code "108") (name "unconnected-(U2-GP12-Pad13)") (class "Default")
      (node (ref "U2") (pin "13") (pinfunction "GP12_13") (pintype "unspecified+no_connect"))
    )
    (net (code "109") (name "unconnected-(U2-GP13-Pad14)") (class "Default")
      (node (ref "U2") (pin "14") (pinfunction "GP13_14") (pintype "unspecified+no_connect"))
    )
    (net (code "110") (name "unconnected-(U2-GP26-Pad17)") (class "Default")
      (node (ref "U2") (pin "17") (pinfunction "GP26_17") (pintype "unspecified+no_connect"))
    )
    (net (code "111") (name "unconnected-(U2-GP29-Pad20)") (class "Default")
      (node (ref "U2") (pin "20") (pinfunction "GP29_20") (pintype "unspecified+no_connect"))
    )
  )
)
